# USB_SATA.net
KiCad netlist of a schematic drawn in Altium Designer
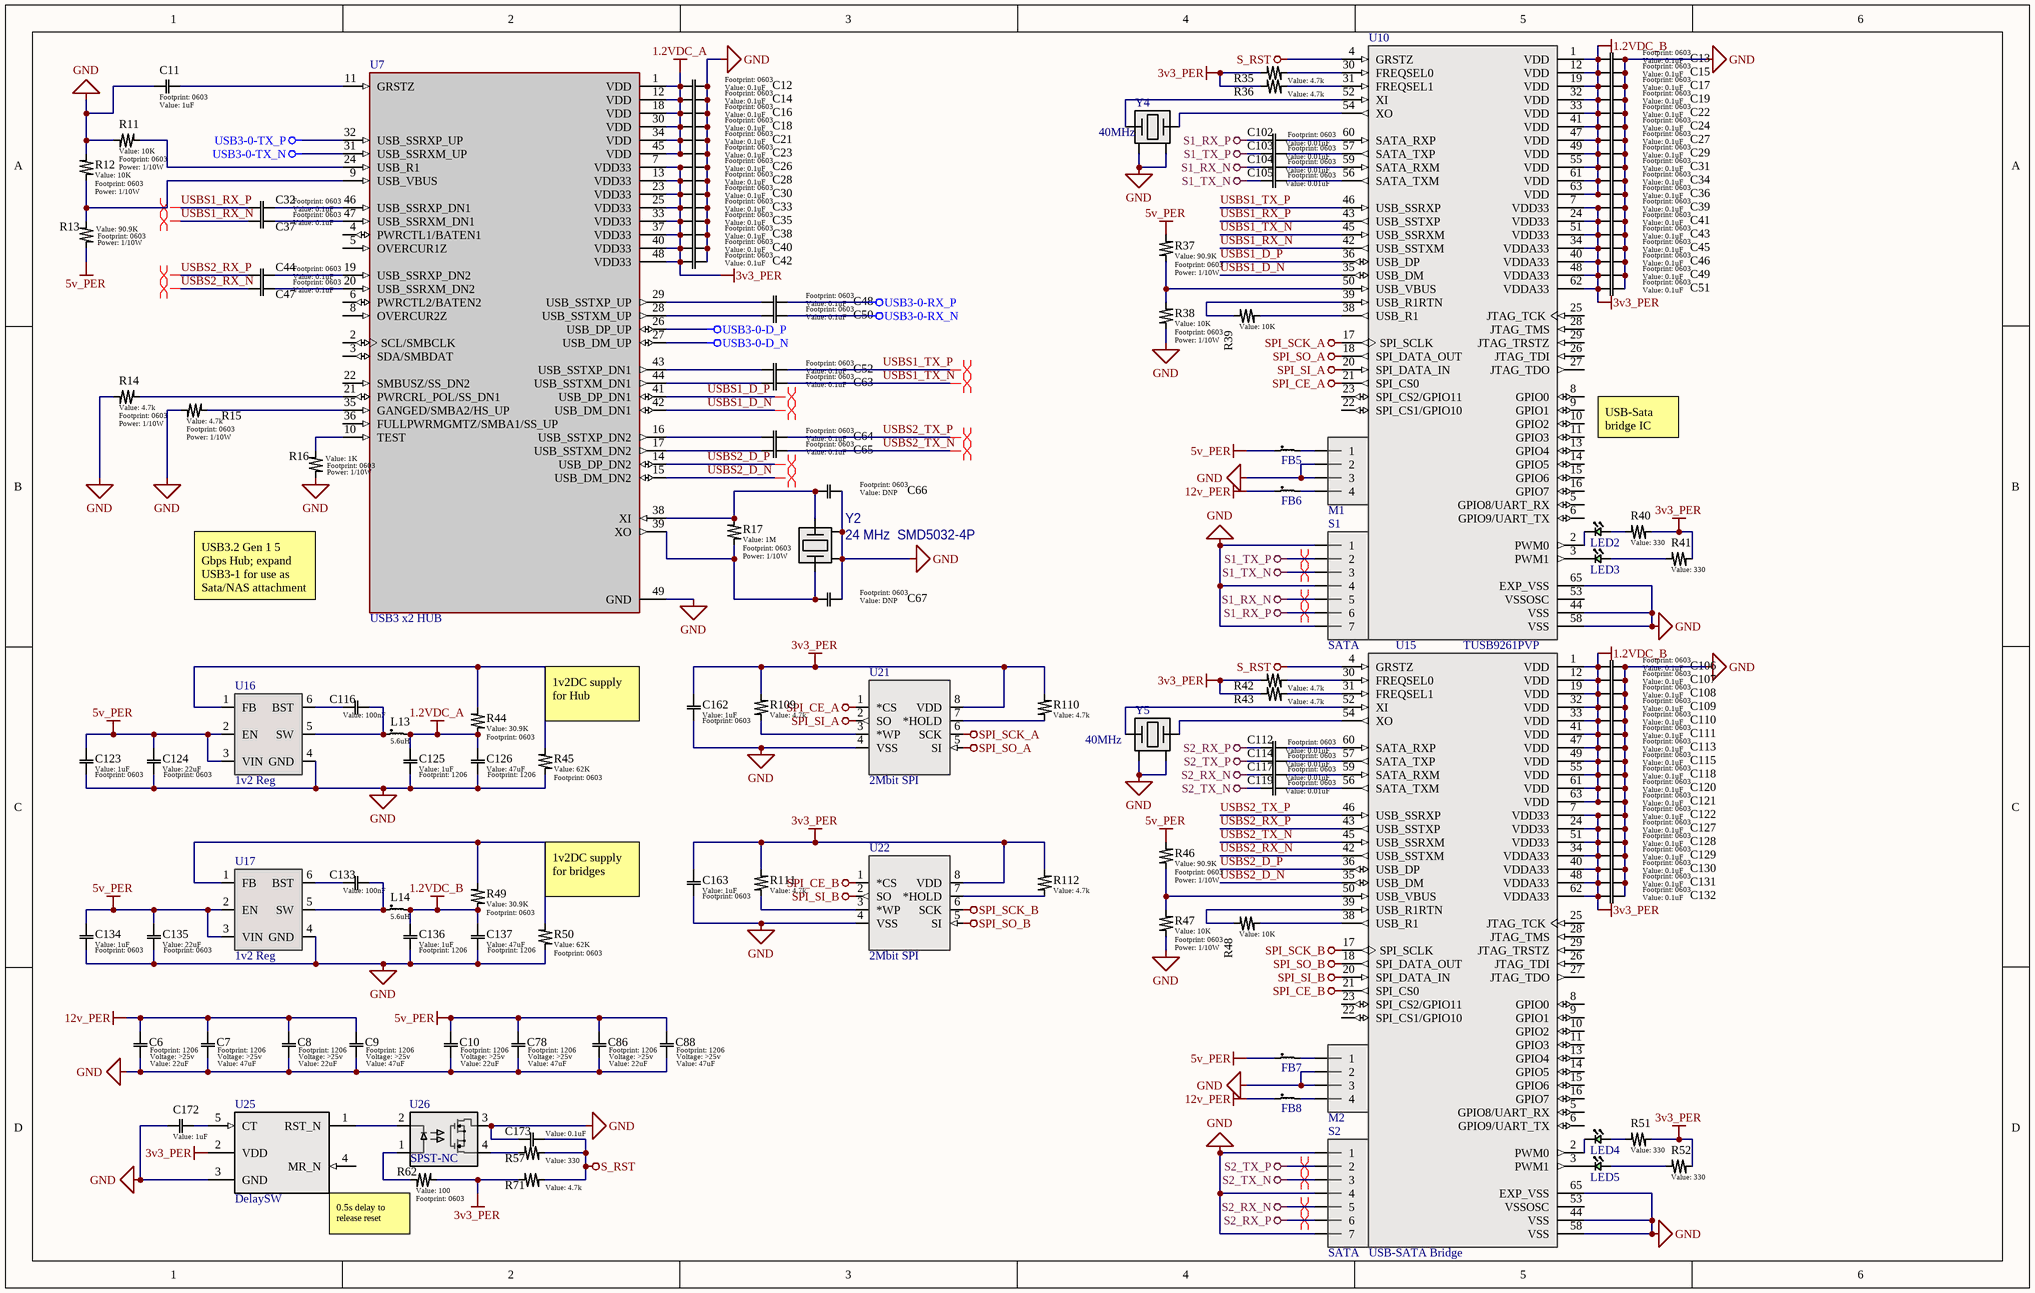
[diagram p0: USB_SATA.SchDoc]

(export (version "E")
  (design (tool "Eeschema 10.0.6"))
  (components
    (comp (ref "C6")
      (value "22uF")
      (footprint "1206")
      (fields
        (field (name "VOLTAGE") ">25v")
        (field (name "TOLERANCE") "20%")
        (field (name "Comment") "Generic Capacitor")
      )
      (libsource (lib "Capacitors") (part "Generic Capacitor"))
    )
    (comp (ref "C7")
      (value "47uF")
      (footprint "1206")
      (fields
        (field (name "VOLTAGE") ">25v")
        (field (name "TOLERANCE") "20%")
        (field (name "Comment") "Generic Capacitor")
      )
      (libsource (lib "Capacitors") (part "Generic Capacitor"))
    )
    (comp (ref "C8")
      (value "22uF")
      (footprint "1206")
      (fields
        (field (name "VOLTAGE") ">25v")
        (field (name "TOLERANCE") "20%")
        (field (name "Comment") "Generic Capacitor")
      )
      (libsource (lib "Capacitors") (part "Generic Capacitor"))
    )
    (comp (ref "C9")
      (value "47uF")
      (footprint "1206")
      (fields
        (field (name "VOLTAGE") ">25v")
        (field (name "TOLERANCE") "20%")
        (field (name "Comment") "Generic Capacitor")
      )
      (libsource (lib "Capacitors") (part "Generic Capacitor"))
    )
    (comp (ref "C10")
      (value "22uF")
      (footprint "1206")
      (fields
        (field (name "VOLTAGE") ">25v")
        (field (name "TOLERANCE") "20%")
        (field (name "Comment") "Generic Capacitor")
      )
      (libsource (lib "Capacitors") (part "Generic Capacitor"))
    )
    (comp (ref "C11")
      (value "1uF")
      (footprint "0603")
      (fields
        (field (name "VOLTAGE") ">10V")
        (field (name "TOLERANCE") "10%")
        (field (name "Comment") "Generic Capacitor")
      )
      (libsource (lib "Capacitors") (part "Generic Capacitor"))
    )
    (comp (ref "C12")
      (value "0.1uF")
      (footprint "0603")
      (fields
        (field (name "VOLTAGE") "10V")
        (field (name "TOLERANCE") "10%")
        (field (name "Comment") "Generic Capacitor")
      )
      (libsource (lib "Capacitors") (part "Generic Capacitor"))
    )
    (comp (ref "C13")
      (value "0.1uF")
      (footprint "0603")
      (fields
        (field (name "VOLTAGE") "10V")
        (field (name "TOLERANCE") "10%")
        (field (name "Comment") "Generic Capacitor")
      )
      (libsource (lib "Capacitors") (part "Generic Capacitor"))
    )
    (comp (ref "C14")
      (value "0.1uF")
      (footprint "0603")
      (fields
        (field (name "VOLTAGE") "10V")
        (field (name "TOLERANCE") "10%")
        (field (name "Comment") "Generic Capacitor")
      )
      (libsource (lib "Capacitors") (part "Generic Capacitor"))
    )
    (comp (ref "C15")
      (value "0.1uF")
      (footprint "0603")
      (fields
        (field (name "VOLTAGE") "10V")
        (field (name "TOLERANCE") "10%")
        (field (name "Comment") "Generic Capacitor")
      )
      (libsource (lib "Capacitors") (part "Generic Capacitor"))
    )
    (comp (ref "C16")
      (value "0.1uF")
      (footprint "0603")
      (fields
        (field (name "VOLTAGE") "10V")
        (field (name "TOLERANCE") "10%")
        (field (name "Comment") "Generic Capacitor")
      )
      (libsource (lib "Capacitors") (part "Generic Capacitor"))
    )
    (comp (ref "C17")
      (value "0.1uF")
      (footprint "0603")
      (fields
        (field (name "VOLTAGE") "10V")
        (field (name "TOLERANCE") "10%")
        (field (name "Comment") "Generic Capacitor")
      )
      (libsource (lib "Capacitors") (part "Generic Capacitor"))
    )
    (comp (ref "C18")
      (value "0.1uF")
      (footprint "0603")
      (fields
        (field (name "VOLTAGE") "10V")
        (field (name "TOLERANCE") "10%")
        (field (name "Comment") "Generic Capacitor")
      )
      (libsource (lib "Capacitors") (part "Generic Capacitor"))
    )
    (comp (ref "C19")
      (value "0.1uF")
      (footprint "0603")
      (fields
        (field (name "VOLTAGE") "10V")
        (field (name "TOLERANCE") "10%")
        (field (name "Comment") "Generic Capacitor")
      )
      (libsource (lib "Capacitors") (part "Generic Capacitor"))
    )
    (comp (ref "C21")
      (value "0.1uF")
      (footprint "0603")
      (fields
        (field (name "VOLTAGE") "10V")
        (field (name "TOLERANCE") "10%")
        (field (name "Comment") "Generic Capacitor")
      )
      (libsource (lib "Capacitors") (part "Generic Capacitor"))
    )
    (comp (ref "C22")
      (value "0.1uF")
      (footprint "0603")
      (fields
        (field (name "VOLTAGE") "10V")
        (field (name "TOLERANCE") "10%")
        (field (name "Comment") "Generic Capacitor")
      )
      (libsource (lib "Capacitors") (part "Generic Capacitor"))
    )
    (comp (ref "C23")
      (value "0.1uF")
      (footprint "0603")
      (fields
        (field (name "VOLTAGE") "10V")
        (field (name "TOLERANCE") "10%")
        (field (name "Comment") "Generic Capacitor")
      )
      (libsource (lib "Capacitors") (part "Generic Capacitor"))
    )
    (comp (ref "C24")
      (value "0.1uF")
      (footprint "0603")
      (fields
        (field (name "VOLTAGE") "10V")
        (field (name "TOLERANCE") "10%")
        (field (name "Comment") "Generic Capacitor")
      )
      (libsource (lib "Capacitors") (part "Generic Capacitor"))
    )
    (comp (ref "C26")
      (value "0.1uF")
      (footprint "0603")
      (fields
        (field (name "VOLTAGE") "10V")
        (field (name "TOLERANCE") "10%")
        (field (name "Comment") "Generic Capacitor")
      )
      (libsource (lib "Capacitors") (part "Generic Capacitor"))
    )
    (comp (ref "C27")
      (value "0.1uF")
      (footprint "0603")
      (fields
        (field (name "VOLTAGE") "10V")
        (field (name "TOLERANCE") "10%")
        (field (name "Comment") "Generic Capacitor")
      )
      (libsource (lib "Capacitors") (part "Generic Capacitor"))
    )
    (comp (ref "C28")
      (value "0.1uF")
      (footprint "0603")
      (fields
        (field (name "VOLTAGE") "10V")
        (field (name "TOLERANCE") "10%")
        (field (name "Comment") "Generic Capacitor")
      )
      (libsource (lib "Capacitors") (part "Generic Capacitor"))
    )
    (comp (ref "C29")
      (value "0.1uF")
      (footprint "0603")
      (fields
        (field (name "VOLTAGE") "10V")
        (field (name "TOLERANCE") "10%")
        (field (name "Comment") "Generic Capacitor")
      )
      (libsource (lib "Capacitors") (part "Generic Capacitor"))
    )
    (comp (ref "C30")
      (value "0.1uF")
      (footprint "0603")
      (fields
        (field (name "VOLTAGE") "10V")
        (field (name "TOLERANCE") "10%")
        (field (name "Comment") "Generic Capacitor")
      )
      (libsource (lib "Capacitors") (part "Generic Capacitor"))
    )
    (comp (ref "C31")
      (value "0.1uF")
      (footprint "0603")
      (fields
        (field (name "VOLTAGE") "10V")
        (field (name "TOLERANCE") "10%")
        (field (name "Comment") "Generic Capacitor")
      )
      (libsource (lib "Capacitors") (part "Generic Capacitor"))
    )
    (comp (ref "C32")
      (value "0.1uF")
      (footprint "0603")
      (fields
        (field (name "VOLTAGE") "10V")
        (field (name "TOLERANCE") "10%")
        (field (name "Comment") "Generic Capacitor")
      )
      (libsource (lib "Capacitors") (part "Generic Capacitor"))
    )
    (comp (ref "C33")
      (value "0.1uF")
      (footprint "0603")
      (fields
        (field (name "VOLTAGE") "10V")
        (field (name "TOLERANCE") "10%")
        (field (name "Comment") "Generic Capacitor")
      )
      (libsource (lib "Capacitors") (part "Generic Capacitor"))
    )
    (comp (ref "C34")
      (value "0.1uF")
      (footprint "0603")
      (fields
        (field (name "VOLTAGE") "10V")
        (field (name "TOLERANCE") "10%")
        (field (name "Comment") "Generic Capacitor")
      )
      (libsource (lib "Capacitors") (part "Generic Capacitor"))
    )
    (comp (ref "C35")
      (value "0.1uF")
      (footprint "0603")
      (fields
        (field (name "VOLTAGE") "10V")
        (field (name "TOLERANCE") "10%")
        (field (name "Comment") "Generic Capacitor")
      )
      (libsource (lib "Capacitors") (part "Generic Capacitor"))
    )
    (comp (ref "C36")
      (value "0.1uF")
      (footprint "0603")
      (fields
        (field (name "VOLTAGE") "10V")
        (field (name "TOLERANCE") "10%")
        (field (name "Comment") "Generic Capacitor")
      )
      (libsource (lib "Capacitors") (part "Generic Capacitor"))
    )
    (comp (ref "C37")
      (value "0.1uF")
      (footprint "0603")
      (fields
        (field (name "VOLTAGE") "10V")
        (field (name "TOLERANCE") "10%")
        (field (name "Comment") "Generic Capacitor")
      )
      (libsource (lib "Capacitors") (part "Generic Capacitor"))
    )
    (comp (ref "C38")
      (value "0.1uF")
      (footprint "0603")
      (fields
        (field (name "VOLTAGE") "10V")
        (field (name "TOLERANCE") "10%")
        (field (name "Comment") "Generic Capacitor")
      )
      (libsource (lib "Capacitors") (part "Generic Capacitor"))
    )
    (comp (ref "C39")
      (value "0.1uF")
      (footprint "0603")
      (fields
        (field (name "VOLTAGE") "10V")
        (field (name "TOLERANCE") "10%")
        (field (name "Comment") "Generic Capacitor")
      )
      (libsource (lib "Capacitors") (part "Generic Capacitor"))
    )
    (comp (ref "C40")
      (value "0.1uF")
      (footprint "0603")
      (fields
        (field (name "VOLTAGE") "10V")
        (field (name "TOLERANCE") "10%")
        (field (name "Comment") "Generic Capacitor")
      )
      (libsource (lib "Capacitors") (part "Generic Capacitor"))
    )
    (comp (ref "C41")
      (value "0.1uF")
      (footprint "0603")
      (fields
        (field (name "VOLTAGE") "10V")
        (field (name "TOLERANCE") "10%")
        (field (name "Comment") "Generic Capacitor")
      )
      (libsource (lib "Capacitors") (part "Generic Capacitor"))
    )
    (comp (ref "C42")
      (value "0.1uF")
      (footprint "0603")
      (fields
        (field (name "VOLTAGE") "10V")
        (field (name "TOLERANCE") "10%")
        (field (name "Comment") "Generic Capacitor")
      )
      (libsource (lib "Capacitors") (part "Generic Capacitor"))
    )
    (comp (ref "C43")
      (value "0.1uF")
      (footprint "0603")
      (fields
        (field (name "VOLTAGE") "10V")
        (field (name "TOLERANCE") "10%")
        (field (name "Comment") "Generic Capacitor")
      )
      (libsource (lib "Capacitors") (part "Generic Capacitor"))
    )
    (comp (ref "C44")
      (value "0.1uF")
      (footprint "0603")
      (fields
        (field (name "VOLTAGE") "10V")
        (field (name "TOLERANCE") "10%")
        (field (name "Comment") "Generic Capacitor")
      )
      (libsource (lib "Capacitors") (part "Generic Capacitor"))
    )
    (comp (ref "C45")
      (value "0.1uF")
      (footprint "0603")
      (fields
        (field (name "VOLTAGE") "10V")
        (field (name "TOLERANCE") "10%")
        (field (name "Comment") "Generic Capacitor")
      )
      (libsource (lib "Capacitors") (part "Generic Capacitor"))
    )
    (comp (ref "C46")
      (value "0.1uF")
      (footprint "0603")
      (fields
        (field (name "VOLTAGE") "10V")
        (field (name "TOLERANCE") "10%")
        (field (name "Comment") "Generic Capacitor")
      )
      (libsource (lib "Capacitors") (part "Generic Capacitor"))
    )
    (comp (ref "C47")
      (value "0.1uF")
      (footprint "0603")
      (fields
        (field (name "VOLTAGE") "10V")
        (field (name "TOLERANCE") "10%")
        (field (name "Comment") "Generic Capacitor")
      )
      (libsource (lib "Capacitors") (part "Generic Capacitor"))
    )
    (comp (ref "C48")
      (value "0.1uF")
      (footprint "0603")
      (fields
        (field (name "VOLTAGE") "10V")
        (field (name "TOLERANCE") "10%")
        (field (name "Comment") "Generic Capacitor")
      )
      (libsource (lib "Capacitors") (part "Generic Capacitor"))
    )
    (comp (ref "C49")
      (value "0.1uF")
      (footprint "0603")
      (fields
        (field (name "VOLTAGE") "10V")
        (field (name "TOLERANCE") "10%")
        (field (name "Comment") "Generic Capacitor")
      )
      (libsource (lib "Capacitors") (part "Generic Capacitor"))
    )
    (comp (ref "C50")
      (value "0.1uF")
      (footprint "0603")
      (fields
        (field (name "VOLTAGE") "10V")
        (field (name "TOLERANCE") "10%")
        (field (name "Comment") "Generic Capacitor")
      )
      (libsource (lib "Capacitors") (part "Generic Capacitor"))
    )
    (comp (ref "C51")
      (value "0.1uF")
      (footprint "0603")
      (fields
        (field (name "VOLTAGE") "10V")
        (field (name "TOLERANCE") "10%")
        (field (name "Comment") "Generic Capacitor")
      )
      (libsource (lib "Capacitors") (part "Generic Capacitor"))
    )
    (comp (ref "C52")
      (value "0.1uF")
      (footprint "0603")
      (fields
        (field (name "VOLTAGE") "10V")
        (field (name "TOLERANCE") "10%")
        (field (name "Comment") "Generic Capacitor")
      )
      (libsource (lib "Capacitors") (part "Generic Capacitor"))
    )
    (comp (ref "C63")
      (value "0.1uF")
      (footprint "0603")
      (fields
        (field (name "VOLTAGE") "10V")
        (field (name "TOLERANCE") "10%")
        (field (name "Comment") "Generic Capacitor")
      )
      (libsource (lib "Capacitors") (part "Generic Capacitor"))
    )
    (comp (ref "C64")
      (value "0.1uF")
      (footprint "0603")
      (fields
        (field (name "VOLTAGE") "10V")
        (field (name "TOLERANCE") "10%")
        (field (name "Comment") "Generic Capacitor")
      )
      (libsource (lib "Capacitors") (part "Generic Capacitor"))
    )
    (comp (ref "C65")
      (value "0.1uF")
      (footprint "0603")
      (fields
        (field (name "VOLTAGE") "10V")
        (field (name "TOLERANCE") "10%")
        (field (name "Comment") "Generic Capacitor")
      )
      (libsource (lib "Capacitors") (part "Generic Capacitor"))
    )
    (comp (ref "C66")
      (value "DNP")
      (footprint "0603")
      (fields
        (field (name "VOLTAGE") ">10V")
        (field (name "TOLERANCE") "10%")
        (field (name "Comment") "Generic Capacitor")
      )
      (libsource (lib "Capacitors") (part "Generic Capacitor"))
    )
    (comp (ref "C67")
      (value "DNP")
      (footprint "0603")
      (fields
        (field (name "VOLTAGE") ">10V")
        (field (name "TOLERANCE") "10%")
        (field (name "Comment") "Generic Capacitor")
      )
      (libsource (lib "Capacitors") (part "Generic Capacitor"))
    )
    (comp (ref "C78")
      (value "47uF")
      (footprint "1206")
      (fields
        (field (name "VOLTAGE") ">25v")
        (field (name "TOLERANCE") "20%")
        (field (name "Comment") "Generic Capacitor")
      )
      (libsource (lib "Capacitors") (part "Generic Capacitor"))
    )
    (comp (ref "C86")
      (value "22uF")
      (footprint "1206")
      (fields
        (field (name "VOLTAGE") ">25v")
        (field (name "TOLERANCE") "20%")
        (field (name "Comment") "Generic Capacitor")
      )
      (libsource (lib "Capacitors") (part "Generic Capacitor"))
    )
    (comp (ref "C88")
      (value "47uF")
      (footprint "1206")
      (fields
        (field (name "VOLTAGE") ">25v")
        (field (name "TOLERANCE") "20%")
        (field (name "Comment") "Generic Capacitor")
      )
      (libsource (lib "Capacitors") (part "Generic Capacitor"))
    )
    (comp (ref "C102")
      (value "0.01uF")
      (footprint "0603")
      (fields
        (field (name "VOLTAGE") "10V")
        (field (name "TOLERANCE") "10%")
        (field (name "Comment") "Generic Capacitor")
      )
      (libsource (lib "Capacitors") (part "Generic Capacitor"))
    )
    (comp (ref "C103")
      (value "0.01uF")
      (footprint "0603")
      (fields
        (field (name "VOLTAGE") "10V")
        (field (name "TOLERANCE") "10%")
        (field (name "Comment") "Generic Capacitor")
      )
      (libsource (lib "Capacitors") (part "Generic Capacitor"))
    )
    (comp (ref "C104")
      (value "0.01uF")
      (footprint "0603")
      (fields
        (field (name "VOLTAGE") "10V")
        (field (name "TOLERANCE") "10%")
        (field (name "Comment") "Generic Capacitor")
      )
      (libsource (lib "Capacitors") (part "Generic Capacitor"))
    )
    (comp (ref "C105")
      (value "0.01uF")
      (footprint "0603")
      (fields
        (field (name "VOLTAGE") "10V")
        (field (name "TOLERANCE") "10%")
        (field (name "Comment") "Generic Capacitor")
      )
      (libsource (lib "Capacitors") (part "Generic Capacitor"))
    )
    (comp (ref "C106")
      (value "0.1uF")
      (footprint "0603")
      (fields
        (field (name "VOLTAGE") "10V")
        (field (name "TOLERANCE") "10%")
        (field (name "Comment") "Generic Capacitor")
      )
      (libsource (lib "Capacitors") (part "Generic Capacitor"))
    )
    (comp (ref "C107")
      (value "0.1uF")
      (footprint "0603")
      (fields
        (field (name "VOLTAGE") "10V")
        (field (name "TOLERANCE") "10%")
        (field (name "Comment") "Generic Capacitor")
      )
      (libsource (lib "Capacitors") (part "Generic Capacitor"))
    )
    (comp (ref "C108")
      (value "0.1uF")
      (footprint "0603")
      (fields
        (field (name "VOLTAGE") "10V")
        (field (name "TOLERANCE") "10%")
        (field (name "Comment") "Generic Capacitor")
      )
      (libsource (lib "Capacitors") (part "Generic Capacitor"))
    )
    (comp (ref "C109")
      (value "0.1uF")
      (footprint "0603")
      (fields
        (field (name "VOLTAGE") "10V")
        (field (name "TOLERANCE") "10%")
        (field (name "Comment") "Generic Capacitor")
      )
      (libsource (lib "Capacitors") (part "Generic Capacitor"))
    )
    (comp (ref "C110")
      (value "0.1uF")
      (footprint "0603")
      (fields
        (field (name "VOLTAGE") "10V")
        (field (name "TOLERANCE") "10%")
        (field (name "Comment") "Generic Capacitor")
      )
      (libsource (lib "Capacitors") (part "Generic Capacitor"))
    )
    (comp (ref "C111")
      (value "0.1uF")
      (footprint "0603")
      (fields
        (field (name "VOLTAGE") "10V")
        (field (name "TOLERANCE") "10%")
        (field (name "Comment") "Generic Capacitor")
      )
      (libsource (lib "Capacitors") (part "Generic Capacitor"))
    )
    (comp (ref "C112")
      (value "0.01uF")
      (footprint "0603")
      (fields
        (field (name "VOLTAGE") "10V")
        (field (name "TOLERANCE") "10%")
        (field (name "Comment") "Generic Capacitor")
      )
      (libsource (lib "Capacitors") (part "Generic Capacitor"))
    )
    (comp (ref "C113")
      (value "0.1uF")
      (footprint "0603")
      (fields
        (field (name "VOLTAGE") "10V")
        (field (name "TOLERANCE") "10%")
        (field (name "Comment") "Generic Capacitor")
      )
      (libsource (lib "Capacitors") (part "Generic Capacitor"))
    )
    (comp (ref "C114")
      (value "0.01uF")
      (footprint "0603")
      (fields
        (field (name "VOLTAGE") "10V")
        (field (name "TOLERANCE") "10%")
        (field (name "Comment") "Generic Capacitor")
      )
      (libsource (lib "Capacitors") (part "Generic Capacitor"))
    )
    (comp (ref "C115")
      (value "0.1uF")
      (footprint "0603")
      (fields
        (field (name "VOLTAGE") "10V")
        (field (name "TOLERANCE") "10%")
        (field (name "Comment") "Generic Capacitor")
      )
      (libsource (lib "Capacitors") (part "Generic Capacitor"))
    )
    (comp (ref "C116")
      (value "100nF")
      (footprint "0603")
      (fields
        (field (name "VOLTAGE") ">10V")
        (field (name "TOLERANCE") "10%")
        (field (name "Comment") "Generic Capacitor")
      )
      (libsource (lib "Capacitors") (part "Generic Capacitor"))
    )
    (comp (ref "C117")
      (value "0.01uF")
      (footprint "0603")
      (fields
        (field (name "VOLTAGE") "10V")
        (field (name "TOLERANCE") "10%")
        (field (name "Comment") "Generic Capacitor")
      )
      (libsource (lib "Capacitors") (part "Generic Capacitor"))
    )
    (comp (ref "C118")
      (value "0.1uF")
      (footprint "0603")
      (fields
        (field (name "VOLTAGE") "10V")
        (field (name "TOLERANCE") "10%")
        (field (name "Comment") "Generic Capacitor")
      )
      (libsource (lib "Capacitors") (part "Generic Capacitor"))
    )
    (comp (ref "C119")
      (value "0.01uF")
      (footprint "0603")
      (fields
        (field (name "VOLTAGE") "10V")
        (field (name "TOLERANCE") "10%")
        (field (name "Comment") "Generic Capacitor")
      )
      (libsource (lib "Capacitors") (part "Generic Capacitor"))
    )
    (comp (ref "C120")
      (value "0.1uF")
      (footprint "0603")
      (fields
        (field (name "VOLTAGE") "10V")
        (field (name "TOLERANCE") "10%")
        (field (name "Comment") "Generic Capacitor")
      )
      (libsource (lib "Capacitors") (part "Generic Capacitor"))
    )
    (comp (ref "C121")
      (value "0.1uF")
      (footprint "0603")
      (fields
        (field (name "VOLTAGE") "10V")
        (field (name "TOLERANCE") "10%")
        (field (name "Comment") "Generic Capacitor")
      )
      (libsource (lib "Capacitors") (part "Generic Capacitor"))
    )
    (comp (ref "C122")
      (value "0.1uF")
      (footprint "0603")
      (fields
        (field (name "VOLTAGE") "10V")
        (field (name "TOLERANCE") "10%")
        (field (name "Comment") "Generic Capacitor")
      )
      (libsource (lib "Capacitors") (part "Generic Capacitor"))
    )
    (comp (ref "C123")
      (value "1uF")
      (footprint "0603")
      (fields
        (field (name "VOLTAGE") ">10V")
        (field (name "TOLERANCE") "10%")
        (field (name "Comment") "Generic Capacitor")
      )
      (libsource (lib "Capacitors") (part "Generic Capacitor"))
    )
    (comp (ref "C124")
      (value "22uF")
      (footprint "0603")
      (fields
        (field (name "VOLTAGE") ">10V")
        (field (name "TOLERANCE") "10%")
        (field (name "Comment") "Generic Capacitor")
      )
      (libsource (lib "Capacitors") (part "Generic Capacitor"))
    )
    (comp (ref "C125")
      (value "1uF")
      (footprint "1206")
      (fields
        (field (name "VOLTAGE") ">10V")
        (field (name "TOLERANCE") "10%")
        (field (name "Comment") "Generic Capacitor")
      )
      (libsource (lib "Capacitors") (part "Generic Capacitor"))
    )
    (comp (ref "C126")
      (value "47uF")
      (footprint "1206")
      (fields
        (field (name "VOLTAGE") ">10V")
        (field (name "TOLERANCE") "10%")
        (field (name "Comment") "Generic Capacitor")
      )
      (libsource (lib "Capacitors") (part "Generic Capacitor"))
    )
    (comp (ref "C127")
      (value "0.1uF")
      (footprint "0603")
      (fields
        (field (name "VOLTAGE") "10V")
        (field (name "TOLERANCE") "10%")
        (field (name "Comment") "Generic Capacitor")
      )
      (libsource (lib "Capacitors") (part "Generic Capacitor"))
    )
    (comp (ref "C128")
      (value "0.1uF")
      (footprint "0603")
      (fields
        (field (name "VOLTAGE") "10V")
        (field (name "TOLERANCE") "10%")
        (field (name "Comment") "Generic Capacitor")
      )
      (libsource (lib "Capacitors") (part "Generic Capacitor"))
    )
    (comp (ref "C129")
      (value "0.1uF")
      (footprint "0603")
      (fields
        (field (name "VOLTAGE") "10V")
        (field (name "TOLERANCE") "10%")
        (field (name "Comment") "Generic Capacitor")
      )
      (libsource (lib "Capacitors") (part "Generic Capacitor"))
    )
    (comp (ref "C130")
      (value "0.1uF")
      (footprint "0603")
      (fields
        (field (name "VOLTAGE") "10V")
        (field (name "TOLERANCE") "10%")
        (field (name "Comment") "Generic Capacitor")
      )
      (libsource (lib "Capacitors") (part "Generic Capacitor"))
    )
    (comp (ref "C131")
      (value "0.1uF")
      (footprint "0603")
      (fields
        (field (name "VOLTAGE") "10V")
        (field (name "TOLERANCE") "10%")
        (field (name "Comment") "Generic Capacitor")
      )
      (libsource (lib "Capacitors") (part "Generic Capacitor"))
    )
    (comp (ref "C132")
      (value "0.1uF")
      (footprint "0603")
      (fields
        (field (name "VOLTAGE") "10V")
        (field (name "TOLERANCE") "10%")
        (field (name "Comment") "Generic Capacitor")
      )
      (libsource (lib "Capacitors") (part "Generic Capacitor"))
    )
    (comp (ref "C133")
      (value "100nF")
      (footprint "0603")
      (fields
        (field (name "VOLTAGE") ">10V")
        (field (name "TOLERANCE") "10%")
        (field (name "Comment") "Generic Capacitor")
      )
      (libsource (lib "Capacitors") (part "Generic Capacitor"))
    )
    (comp (ref "C134")
      (value "1uF")
      (footprint "0603")
      (fields
        (field (name "VOLTAGE") ">10V")
        (field (name "TOLERANCE") "10%")
        (field (name "Comment") "Generic Capacitor")
      )
      (libsource (lib "Capacitors") (part "Generic Capacitor"))
    )
    (comp (ref "C135")
      (value "22uF")
      (footprint "0603")
      (fields
        (field (name "VOLTAGE") ">10V")
        (field (name "TOLERANCE") "10%")
        (field (name "Comment") "Generic Capacitor")
      )
      (libsource (lib "Capacitors") (part "Generic Capacitor"))
    )
    (comp (ref "C136")
      (value "1uF")
      (footprint "1206")
      (fields
        (field (name "VOLTAGE") ">10V")
        (field (name "TOLERANCE") "10%")
        (field (name "Comment") "Generic Capacitor")
      )
      (libsource (lib "Capacitors") (part "Generic Capacitor"))
    )
    (comp (ref "C137")
      (value "47uF")
      (footprint "1206")
      (fields
        (field (name "VOLTAGE") ">10V")
        (field (name "TOLERANCE") "10%")
        (field (name "Comment") "Generic Capacitor")
      )
      (libsource (lib "Capacitors") (part "Generic Capacitor"))
    )
    (comp (ref "C162")
      (value "1uF")
      (footprint "0603")
      (fields
        (field (name "VOLTAGE") ">10V")
        (field (name "TOLERANCE") "10%")
        (field (name "Comment") "Generic Capacitor")
      )
      (libsource (lib "Capacitors") (part "Generic Capacitor"))
    )
    (comp (ref "C163")
      (value "1uF")
      (footprint "0603")
      (fields
        (field (name "VOLTAGE") ">10V")
        (field (name "TOLERANCE") "10%")
        (field (name "Comment") "Generic Capacitor")
      )
      (libsource (lib "Capacitors") (part "Generic Capacitor"))
    )
    (comp (ref "C172")
      (value "1uF")
      (footprint "0603")
      (fields
        (field (name "VOLTAGE") "10V")
        (field (name "TOLERANCE") "10%")
        (field (name "Comment") "Generic Capacitor")
      )
      (libsource (lib "Capacitors") (part "Generic Capacitor"))
    )
    (comp (ref "C173")
      (value "0.1uF")
      (footprint "0603")
      (fields
        (field (name "VOLTAGE") "10V")
        (field (name "TOLERANCE") "10%")
        (field (name "Comment") "Generic Capacitor")
      )
      (libsource (lib "Capacitors") (part "Generic Capacitor"))
    )
    (comp (ref "FB5")
      (value "1206 Ferrite")
      (footprint "1206")
      (description "160 Ohms @ 100MHz 1 Power, Signal Line Ferrite Bead 1206 (3216 Metric) 6A 18mOhm")
      (libsource (lib "Inductors") (part "HI1206T161R-10"))
    )
    (comp (ref "FB6")
      (value "1206 Ferrite")
      (footprint "1206")
      (description "160 Ohms @ 100MHz 1 Power, Signal Line Ferrite Bead 1206 (3216 Metric) 6A 18mOhm")
      (libsource (lib "Inductors") (part "HI1206T161R-10"))
    )
    (comp (ref "FB7")
      (value "1206 Ferrite")
      (footprint "1206")
      (description "160 Ohms @ 100MHz 1 Power, Signal Line Ferrite Bead 1206 (3216 Metric) 6A 18mOhm")
      (libsource (lib "Inductors") (part "HI1206T161R-10"))
    )
    (comp (ref "FB8")
      (value "1206 Ferrite")
      (footprint "1206")
      (description "160 Ohms @ 100MHz 1 Power, Signal Line Ferrite Bead 1206 (3216 Metric) 6A 18mOhm")
      (libsource (lib "Inductors") (part "HI1206T161R-10"))
    )
    (comp (ref "L13")
      (value "5.6uH")
      (footprint "TMPC0402HP")
      (description "2A 5.6uH ±20% SMD Power Inductor")
      (libsource (lib "Inductors") (part "TMPC0402HP-5R6MG-Z02"))
    )
    (comp (ref "L14")
      (value "5.6uH")
      (footprint "TMPC0402HP")
      (description "2A 5.6uH ±20% SMD Power Inductor")
      (libsource (lib "Inductors") (part "TMPC0402HP-5R6MG-Z02"))
    )
    (comp (ref "LED2")
      (value "LTST-C191KGKT")
      (footprint "0603 (1608 Metric) Concave")
      (description "LED Uni-Color Green 574nm 2-Pin Chip LED T/R")
      (libsource (lib "Gamber - Johnson LLC") (part "LTST-C191KGKT"))
    )
    (comp (ref "LED3")
      (value "LTST-C191KGKT")
      (footprint "0603 (1608 Metric) Concave")
      (description "LED Uni-Color Green 574nm 2-Pin Chip LED T/R")
      (libsource (lib "Gamber - Johnson LLC") (part "LTST-C191KGKT"))
    )
    (comp (ref "LED4")
      (value "LTST-C191KGKT")
      (footprint "0603 (1608 Metric) Concave")
      (description "LED Uni-Color Green 574nm 2-Pin Chip LED T/R")
      (libsource (lib "Gamber - Johnson LLC") (part "LTST-C191KGKT"))
    )
    (comp (ref "LED5")
      (value "LTST-C191KGKT")
      (footprint "0603 (1608 Metric) Concave")
      (description "LED Uni-Color Green 574nm 2-Pin Chip LED T/R")
      (libsource (lib "Gamber - Johnson LLC") (part "LTST-C191KGKT"))
    )
    (comp (ref "M1")
      (value "MATE-n-Lock")
      (footprint "794287-1")
      (description "4 Position Header Connector 0.200\" (5.08mm) Through Hole Tin")
      (libsource (lib "Connectors") (part "794287-1"))
    )
    (comp (ref "M2")
      (value "MATE-n-Lock")
      (footprint "794287-1")
      (description "4 Position Header Connector 0.200\" (5.08mm) Through Hole Tin")
      (libsource (lib "Connectors") (part "794287-1"))
    )
    (comp (ref "R11")
      (value "10K")
      (footprint "0603")
      (fields
        (field (name "TOLERANCE") "1%")
        (field (name "POWER") "1/10W")
        (field (name "Comment") "Generic Resistor")
      )
      (libsource (lib "Resistors") (part "Generic Resistor"))
    )
    (comp (ref "R12")
      (value "10K")
      (footprint "0603")
      (fields
        (field (name "TOLERANCE") "1%")
        (field (name "POWER") "1/10W")
        (field (name "Comment") "Generic Resistor")
      )
      (libsource (lib "Resistors") (part "Generic Resistor"))
    )
    (comp (ref "R13")
      (value "90.9K")
      (footprint "0603")
      (fields
        (field (name "TOLERANCE") "1%")
        (field (name "POWER") "1/10W")
        (field (name "Comment") "Generic Resistor")
      )
      (libsource (lib "Resistors") (part "Generic Resistor"))
    )
    (comp (ref "R14")
      (value "4.7k")
      (footprint "0603")
      (fields
        (field (name "TOLERANCE") "1%")
        (field (name "POWER") "1/10W")
        (field (name "Comment") "Generic Resistor")
      )
      (libsource (lib "Resistors") (part "Generic Resistor"))
    )
    (comp (ref "R15")
      (value "4.7k")
      (footprint "0603")
      (fields
        (field (name "TOLERANCE") "1%")
        (field (name "POWER") "1/10W")
        (field (name "Comment") "Generic Resistor")
      )
      (libsource (lib "Resistors") (part "Generic Resistor"))
    )
    (comp (ref "R16")
      (value "1K")
      (footprint "0603")
      (fields
        (field (name "TOLERANCE") "1%")
        (field (name "POWER") "1/10W")
        (field (name "Comment") "Generic Resistor")
      )
      (libsource (lib "Resistors") (part "Generic Resistor"))
    )
    (comp (ref "R17")
      (value "1M")
      (footprint "0603")
      (fields
        (field (name "TOLERANCE") "1%")
        (field (name "POWER") "1/10W")
        (field (name "Comment") "Generic Resistor")
      )
      (libsource (lib "Resistors") (part "Generic Resistor"))
    )
    (comp (ref "R35")
      (value "4.7k")
      (footprint "0603")
      (fields
        (field (name "TOLERANCE") "1%")
        (field (name "POWER") "1/10W")
        (field (name "Comment") "Generic Resistor")
      )
      (libsource (lib "Resistors") (part "Generic Resistor"))
    )
    (comp (ref "R36")
      (value "4.7k")
      (footprint "0603")
      (fields
        (field (name "TOLERANCE") "1%")
        (field (name "POWER") "1/10W")
        (field (name "Comment") "Generic Resistor")
      )
      (libsource (lib "Resistors") (part "Generic Resistor"))
    )
    (comp (ref "R37")
      (value "90.9K")
      (footprint "0603")
      (fields
        (field (name "TOLERANCE") "1%")
        (field (name "POWER") "1/10W")
        (field (name "Comment") "Generic Resistor")
      )
      (libsource (lib "Resistors") (part "Generic Resistor"))
    )
    (comp (ref "R38")
      (value "10K")
      (footprint "0603")
      (fields
        (field (name "TOLERANCE") "1%")
        (field (name "POWER") "1/10W")
        (field (name "Comment") "Generic Resistor")
      )
      (libsource (lib "Resistors") (part "Generic Resistor"))
    )
    (comp (ref "R39")
      (value "10K")
      (footprint "0603")
      (fields
        (field (name "TOLERANCE") "1%")
        (field (name "POWER") "1/10W")
        (field (name "Comment") "Generic Resistor")
      )
      (libsource (lib "Resistors") (part "Generic Resistor"))
    )
    (comp (ref "R40")
      (value "330")
      (footprint "0603")
      (fields
        (field (name "TOLERANCE") "1%")
        (field (name "POWER") "1/10W")
        (field (name "Comment") "Generic Resistor")
      )
      (libsource (lib "Resistors") (part "Generic Resistor"))
    )
    (comp (ref "R41")
      (value "330")
      (footprint "0603")
      (fields
        (field (name "TOLERANCE") "1%")
        (field (name "POWER") "1/10W")
        (field (name "Comment") "Generic Resistor")
      )
      (libsource (lib "Resistors") (part "Generic Resistor"))
    )
    (comp (ref "R42")
      (value "4.7k")
      (footprint "0603")
      (fields
        (field (name "TOLERANCE") "1%")
        (field (name "POWER") "1/10W")
        (field (name "Comment") "Generic Resistor")
      )
      (libsource (lib "Resistors") (part "Generic Resistor"))
    )
    (comp (ref "R43")
      (value "4.7k")
      (footprint "0603")
      (fields
        (field (name "TOLERANCE") "1%")
        (field (name "POWER") "1/10W")
        (field (name "Comment") "Generic Resistor")
      )
      (libsource (lib "Resistors") (part "Generic Resistor"))
    )
    (comp (ref "R44")
      (value "30.9K")
      (footprint "0603")
      (fields
        (field (name "TOLERANCE") "1%")
        (field (name "POWER") "1/10W")
        (field (name "Comment") "Generic Resistor")
      )
      (libsource (lib "Resistors") (part "Generic Resistor"))
    )
    (comp (ref "R45")
      (value "62K")
      (footprint "0603")
      (fields
        (field (name "TOLERANCE") "1%")
        (field (name "POWER") "1/10W")
        (field (name "Comment") "Generic Resistor")
      )
      (libsource (lib "Resistors") (part "Generic Resistor"))
    )
    (comp (ref "R46")
      (value "90.9K")
      (footprint "0603")
      (fields
        (field (name "TOLERANCE") "1%")
        (field (name "POWER") "1/10W")
        (field (name "Comment") "Generic Resistor")
      )
      (libsource (lib "Resistors") (part "Generic Resistor"))
    )
    (comp (ref "R47")
      (value "10K")
      (footprint "0603")
      (fields
        (field (name "TOLERANCE") "1%")
        (field (name "POWER") "1/10W")
        (field (name "Comment") "Generic Resistor")
      )
      (libsource (lib "Resistors") (part "Generic Resistor"))
    )
    (comp (ref "R48")
      (value "10K")
      (footprint "0603")
      (fields
        (field (name "TOLERANCE") "1%")
        (field (name "POWER") "1/10W")
        (field (name "Comment") "Generic Resistor")
      )
      (libsource (lib "Resistors") (part "Generic Resistor"))
    )
    (comp (ref "R49")
      (value "30.9K")
      (footprint "0603")
      (fields
        (field (name "TOLERANCE") "1%")
        (field (name "POWER") "1/10W")
        (field (name "Comment") "Generic Resistor")
      )
      (libsource (lib "Resistors") (part "Generic Resistor"))
    )
    (comp (ref "R50")
      (value "62K")
      (footprint "0603")
      (fields
        (field (name "TOLERANCE") "1%")
        (field (name "POWER") "1/10W")
        (field (name "Comment") "Generic Resistor")
      )
      (libsource (lib "Resistors") (part "Generic Resistor"))
    )
    (comp (ref "R51")
      (value "330")
      (footprint "0603")
      (fields
        (field (name "TOLERANCE") "1%")
        (field (name "POWER") "1/10W")
        (field (name "Comment") "Generic Resistor")
      )
      (libsource (lib "Resistors") (part "Generic Resistor"))
    )
    (comp (ref "R52")
      (value "330")
      (footprint "0603")
      (fields
        (field (name "TOLERANCE") "1%")
        (field (name "POWER") "1/10W")
        (field (name "Comment") "Generic Resistor")
      )
      (libsource (lib "Resistors") (part "Generic Resistor"))
    )
    (comp (ref "R57")
      (value "330")
      (footprint "0603")
      (fields
        (field (name "TOLERANCE") "1%")
        (field (name "POWER") "1/10W")
        (field (name "Comment") "Generic Resistor")
      )
      (libsource (lib "Resistors") (part "Generic Resistor"))
    )
    (comp (ref "R62")
      (value "100")
      (footprint "0603")
      (fields
        (field (name "TOLERANCE") "1%")
        (field (name "POWER") "1/10W")
        (field (name "Comment") "Generic Resistor")
      )
      (libsource (lib "Resistors") (part "Generic Resistor"))
    )
    (comp (ref "R71")
      (value "4.7k")
      (footprint "0603")
      (fields
        (field (name "TOLERANCE") "1%")
        (field (name "POWER") "1/10W")
        (field (name "Comment") "Generic Resistor")
      )
      (libsource (lib "Resistors") (part "Generic Resistor"))
    )
    (comp (ref "R109")
      (value "4.7k")
      (footprint "0603")
      (fields
        (field (name "TOLERANCE") "1%")
        (field (name "POWER") "1/10W")
        (field (name "Comment") "Generic Resistor")
      )
      (libsource (lib "Resistors") (part "Generic Resistor"))
    )
    (comp (ref "R110")
      (value "4.7k")
      (footprint "0603")
      (fields
        (field (name "TOLERANCE") "1%")
        (field (name "POWER") "1/10W")
        (field (name "Comment") "Generic Resistor")
      )
      (libsource (lib "Resistors") (part "Generic Resistor"))
    )
    (comp (ref "R111")
      (value "4.7k")
      (footprint "0603")
      (fields
        (field (name "TOLERANCE") "1%")
        (field (name "POWER") "1/10W")
        (field (name "Comment") "Generic Resistor")
      )
      (libsource (lib "Resistors") (part "Generic Resistor"))
    )
    (comp (ref "R112")
      (value "4.7k")
      (footprint "0603")
      (fields
        (field (name "TOLERANCE") "1%")
        (field (name "POWER") "1/10W")
        (field (name "Comment") "Generic Resistor")
      )
      (libsource (lib "Resistors") (part "Generic Resistor"))
    )
    (comp (ref "S1")
      (value "SATA")
      (footprint "67800-8025")
      (description "7 Position SATA Header, Shrouded Connector Solder Through Hole")
      (libsource (lib "Connectors") (part "67800-8025"))
    )
    (comp (ref "S2")
      (value "SATA")
      (footprint "67800-8025")
      (description "7 Position SATA Header, Shrouded Connector Solder Through Hole")
      (libsource (lib "Connectors") (part "67800-8025"))
    )
    (comp (ref "U7")
      (value "USB3 x2 HUB")
      (footprint "HTQFP-48(7x7)")
      (description "USB Hub Controller USB 3.0")
      (libsource (lib "Hub ICs") (part "TUSB8020BPHP"))
    )
    (comp (ref "U10")
      (value "USB-SATA Bridge")
      (footprint "64-HTQFP (7x7)")
      (description "HDD, CD, DVD Drive Interface 64-HTQFP _7x7_")
      (fields
        (field (name "MF") "Texas Instruments")
        (field (name "DIGI-KEY_PART_NUMBER") "296-28827-ND")
        (field (name "MP") "TUSB9261PVP")
      )
      (libsource (lib "Misc ICs") (part "TUSB9261PVP"))
    )
    (comp (ref "U15")
      (value "USB-SATA Bridge")
      (footprint "64-HTQFP (7x7)")
      (description "HDD, CD, DVD Drive Interface 64-HTQFP _7x7_")
      (fields (field (name "MF") "Texas Instruments") (field (name "DIGI-KEY_PART_NUMBER") "296-28827-ND"))
      (libsource (lib "Misc ICs") (part "TUSB9261PVP"))
    )
    (comp (ref "U16")
      (value "1v2 Reg")
      (footprint "TSOT-23-6")
      (description "Step-down type Adjustable 2A 1.2V~12V 3.8V~32V TSOT-23-6 DC-DC Converter")
      (libsource (lib "Regulators") (part "AP63201WU-7"))
    )
    (comp (ref "U17")
      (value "1v2 Reg")
      (footprint "TSOT-23-6")
      (description "Step-down type Adjustable 2A 1.2V~12V 3.8V~32V TSOT-23-6 DC-DC Converter")
      (libsource (lib "Regulators") (part "AP63201WU-7"))
    )
    (comp (ref "U21")
      (value "2Mbit SPI")
      (footprint "8-SOIC (0.154\", 3.90mm Width)")
      (description "IC FLASH 2MBIT SPI 30MHZ 8SOP")
      (libsource (lib "Misc ICs") (part "LE25U20AMB-AH"))
    )
    (comp (ref "U22")
      (value "2Mbit SPI")
      (footprint "8-SOIC (0.154\", 3.90mm Width)")
      (description "IC FLASH 2MBIT SPI 30MHZ 8SOP")
      (libsource (lib "Misc ICs") (part "LE25U20AMB-AH"))
    )
    (comp (ref "U25")
      (value "DelaySW")
      (footprint "TSOT-23-5")
      (description "Supervisor Open Drain or Open Collector 1 Channel SOT-23-5\r\n2.2V Threshold")
      (libsource (lib "Switches") (part "TPS3840DL22DBVR"))
    )
    (comp (ref "U26")
      (value "SPST-NC")
      (footprint "4-SOP")
      (description "SSR RELAY SPST-NC 400MA 0-60V")
      (libsource (lib "Switches") (part "CPC1117N"))
    )
    (comp (ref "Y2")
      (value "24 MHz  SMD5032-4P")
      (footprint "ECS-240-18-30BQ-DS")
      (description "24 MHz ±30ppm Crystal 18pF 30 Ohms 4-SMD, No Lead")
      (libsource (lib "Gamber - Johnson LLC") (part "ECS-240-18-30BQ-DS"))
    )
    (comp (ref "Y4")
      (value "40MHz")
      (footprint "SMD3225-4P")
      (description "40MHz Surface Mount Crystal 10pF ±10ppm SMD3225-4P Crystal")
      (libsource (lib "Clock ICs") (part "L327S400H11L"))
    )
    (comp (ref "Y5")
      (value "40MHz")
      (footprint "SMD3225-4P")
      (description "40MHz Surface Mount Crystal 10pF ±10ppm SMD3225-4P Crystal")
      (libsource (lib "Clock ICs") (part "L327S400H11L"))
    )
  )
  (nets
    (net (code "1") (name "/USBS1_D_N") (class "Default")
      (node (ref "U10") (pin "35") (pinfunction "USB_DM_35") (pintype "bidirectional"))
      (node (ref "U7") (pin "42") (pinfunction "USB_DM_DN1_42") (pintype "bidirectional"))
    )
    (net (code "2") (name "/USBS1_D_P") (class "Default")
      (node (ref "U10") (pin "36") (pinfunction "USB_DP_36") (pintype "bidirectional"))
      (node (ref "U7") (pin "41") (pinfunction "USB_DP_DN1_41") (pintype "bidirectional"))
    )
    (net (code "3") (name "/USBS1_RX_N") (class "Default")
      (node (ref "C37") (pin "2") (pinfunction "2_2") (pintype "passive"))
      (node (ref "U10") (pin "42") (pinfunction "USB_SSTXM_42") (pintype "output"))
    )
    (net (code "4") (name "/USBS1_RX_P") (class "Default")
      (node (ref "C32") (pin "2") (pinfunction "2_2") (pintype "passive"))
      (node (ref "U10") (pin "43") (pinfunction "USB_SSTXP_43") (pintype "output"))
    )
    (net (code "5") (name "/USBS1_TX_N") (class "Default")
      (node (ref "C63") (pin "1") (pinfunction "1_1") (pintype "passive"))
      (node (ref "U10") (pin "45") (pinfunction "USB_SSRXM_45") (pintype "input"))
    )
    (net (code "6") (name "/USBS1_TX_P") (class "Default")
      (node (ref "C52") (pin "1") (pinfunction "1_1") (pintype "passive"))
      (node (ref "U10") (pin "46") (pinfunction "USB_SSRXP_46") (pintype "input"))
    )
    (net (code "7") (name "/USBS2_D_N") (class "Default")
      (node (ref "U15") (pin "35") (pinfunction "USB_DM_35") (pintype "bidirectional"))
      (node (ref "U7") (pin "15") (pinfunction "USB_DM_DN2_15") (pintype "bidirectional"))
    )
    (net (code "8") (name "/USBS2_D_P") (class "Default")
      (node (ref "U15") (pin "36") (pinfunction "USB_DP_36") (pintype "bidirectional"))
      (node (ref "U7") (pin "14") (pinfunction "USB_DP_DN2_14") (pintype "bidirectional"))
    )
    (net (code "9") (name "/USBS2_RX_N") (class "Default")
      (node (ref "C47") (pin "2") (pinfunction "2_2") (pintype "passive"))
      (node (ref "U15") (pin "42") (pinfunction "USB_SSTXM_42") (pintype "output"))
    )
    (net (code "10") (name "/USBS2_RX_P") (class "Default")
      (node (ref "C44") (pin "2") (pinfunction "2_2") (pintype "passive"))
      (node (ref "U15") (pin "43") (pinfunction "USB_SSTXP_43") (pintype "output"))
    )
    (net (code "11") (name "/USBS2_TX_N") (class "Default")
      (node (ref "C65") (pin "1") (pinfunction "1_1") (pintype "passive"))
      (node (ref "U15") (pin "45") (pinfunction "USB_SSRXM_45") (pintype "input"))
    )
    (net (code "12") (name "/USBS2_TX_P") (class "Default")
      (node (ref "C64") (pin "1") (pinfunction "1_1") (pintype "passive"))
      (node (ref "U15") (pin "46") (pinfunction "USB_SSRXP_46") (pintype "input"))
    )
    (net (code "13") (name "1.2VDC_A") (class "Default")
      (node (ref "C12") (pin "2") (pinfunction "2_2") (pintype "passive"))
      (node (ref "C125") (pin "1") (pinfunction "1_1") (pintype "passive"))
      (node (ref "C126") (pin "1") (pinfunction "1_1") (pintype "passive"))
      (node (ref "C14") (pin "2") (pinfunction "2_2") (pintype "passive"))
      (node (ref "C16") (pin "2") (pinfunction "2_2") (pintype "passive"))
      (node (ref "C18") (pin "2") (pinfunction "2_2") (pintype "passive"))
      (node (ref "C21") (pin "2") (pinfunction "2_2") (pintype "passive"))
      (node (ref "C23") (pin "2") (pinfunction "2_2") (pintype "passive"))
      (node (ref "L13") (pin "2") (pinfunction "2_2") (pintype "passive"))
      (node (ref "R44") (pin "1") (pinfunction "1_1") (pintype "passive"))
      (node (ref "U7") (pin "1") (pinfunction "VDD_1") (pintype "power_in"))
      (node (ref "U7") (pin "12") (pinfunction "VDD_12") (pintype "power_in"))
      (node (ref "U7") (pin "18") (pinfunction "VDD_18") (pintype "power_in"))
      (node (ref "U7") (pin "30") (pinfunction "VDD_30") (pintype "power_in"))
      (node (ref "U7") (pin "34") (pinfunction "VDD_34") (pintype "power_in"))
      (node (ref "U7") (pin "45") (pinfunction "VDD_45") (pintype "power_in"))
    )
    (net (code "14") (name "1.2VDC_B") (class "Default")
      (node (ref "C106") (pin "2") (pinfunction "2_2") (pintype "passive"))
      (node (ref "C107") (pin "2") (pinfunction "2_2") (pintype "passive"))
      (node (ref "C108") (pin "2") (pinfunction "2_2") (pintype "passive"))
      (node (ref "C109") (pin "2") (pinfunction "2_2") (pintype "passive"))
      (node (ref "C110") (pin "2") (pinfunction "2_2") (pintype "passive"))
      (node (ref "C111") (pin "2") (pinfunction "2_2") (pintype "passive"))
      (node (ref "C113") (pin "2") (pinfunction "2_2") (pintype "passive"))
      (node (ref "C115") (pin "2") (pinfunction "2_2") (pintype "passive"))
      (node (ref "C118") (pin "2") (pinfunction "2_2") (pintype "passive"))
      (node (ref "C120") (pin "2") (pinfunction "2_2") (pintype "passive"))
      (node (ref "C121") (pin "2") (pinfunction "2_2") (pintype "passive"))
      (node (ref "C13") (pin "2") (pinfunction "2_2") (pintype "passive"))
      (node (ref "C136") (pin "1") (pinfunction "1_1") (pintype "passive"))
      (node (ref "C137") (pin "1") (pinfunction "1_1") (pintype "passive"))
      (node (ref "C15") (pin "2") (pinfunction "2_2") (pintype "passive"))
      (node (ref "C17") (pin "2") (pinfunction "2_2") (pintype "passive"))
      (node (ref "C19") (pin "2") (pinfunction "2_2") (pintype "passive"))
      (node (ref "C22") (pin "2") (pinfunction "2_2") (pintype "passive"))
      (node (ref "C24") (pin "2") (pinfunction "2_2") (pintype "passive"))
      (node (ref "C27") (pin "2") (pinfunction "2_2") (pintype "passive"))
      (node (ref "C29") (pin "2") (pinfunction "2_2") (pintype "passive"))
      (node (ref "C31") (pin "2") (pinfunction "2_2") (pintype "passive"))
      (node (ref "C34") (pin "2") (pinfunction "2_2") (pintype "passive"))
      (node (ref "C36") (pin "2") (pinfunction "2_2") (pintype "passive"))
      (node (ref "L14") (pin "2") (pinfunction "2_2") (pintype "passive"))
      (node (ref "R49") (pin "1") (pinfunction "1_1") (pintype "passive"))
      (node (ref "U10") (pin "1") (pinfunction "VDD_1") (pintype "power_in"))
      (node (ref "U10") (pin "12") (pinfunction "VDD_12") (pintype "power_in"))
      (node (ref "U10") (pin "19") (pinfunction "VDD_19") (pintype "power_in"))
      (node (ref "U10") (pin "32") (pinfunction "VDD_32") (pintype "power_in"))
      (node (ref "U10") (pin "33") (pinfunction "VDD_33") (pintype "power_in"))
      (node (ref "U10") (pin "41") (pinfunction "VDD_41") (pintype "power_in"))
      (node (ref "U10") (pin "47") (pinfunction "VDD_47") (pintype "power_in"))
      (node (ref "U10") (pin "49") (pinfunction "VDD_49") (pintype "power_in"))
      (node (ref "U10") (pin "55") (pinfunction "VDD_55") (pintype "power_in"))
      (node (ref "U10") (pin "61") (pinfunction "VDD_61") (pintype "power_in"))
      (node (ref "U10") (pin "63") (pinfunction "VDD_63") (pintype "power_in"))
      (node (ref "U15") (pin "1") (pinfunction "VDD_1") (pintype "power_in"))
      (node (ref "U15") (pin "12") (pinfunction "VDD_12") (pintype "power_in"))
      (node (ref "U15") (pin "19") (pinfunction "VDD_19") (pintype "power_in"))
      (node (ref "U15") (pin "32") (pinfunction "VDD_32") (pintype "power_in"))
      (node (ref "U15") (pin "33") (pinfunction "VDD_33") (pintype "power_in"))
      (node (ref "U15") (pin "41") (pinfunction "VDD_41") (pintype "power_in"))
      (node (ref "U15") (pin "47") (pinfunction "VDD_47") (pintype "power_in"))
      (node (ref "U15") (pin "49") (pinfunction "VDD_49") (pintype "power_in"))
      (node (ref "U15") (pin "55") (pinfunction "VDD_55") (pintype "power_in"))
      (node (ref "U15") (pin "61") (pinfunction "VDD_61") (pintype "power_in"))
      (node (ref "U15") (pin "63") (pinfunction "VDD_63") (pintype "power_in"))
    )
    (net (code "15") (name "3v3_PER") (class "Default")
      (node (ref "C122") (pin "2") (pinfunction "2_2") (pintype "passive"))
      (node (ref "C127") (pin "2") (pinfunction "2_2") (pintype "passive"))
      (node (ref "C128") (pin "2") (pinfunction "2_2") (pintype "passive"))
      (node (ref "C129") (pin "2") (pinfunction "2_2") (pintype "passive"))
      (node (ref "C130") (pin "2") (pinfunction "2_2") (pintype "passive"))
      (node (ref "C131") (pin "2") (pinfunction "2_2") (pintype "passive"))
      (node (ref "C132") (pin "2") (pinfunction "2_2") (pintype "passive"))
      (node (ref "C162") (pin "1") (pinfunction "1_1") (pintype "passive"))
      (node (ref "C163") (pin "1") (pinfunction "1_1") (pintype "passive"))
      (node (ref "C26") (pin "2") (pinfunction "2_2") (pintype "passive"))
      (node (ref "C28") (pin "2") (pinfunction "2_2") (pintype "passive"))
      (node (ref "C30") (pin "2") (pinfunction "2_2") (pintype "passive"))
      (node (ref "C33") (pin "2") (pinfunction "2_2") (pintype "passive"))
      (node (ref "C35") (pin "2") (pinfunction "2_2") (pintype "passive"))
      (node (ref "C38") (pin "2") (pinfunction "2_2") (pintype "passive"))
      (node (ref "C39") (pin "2") (pinfunction "2_2") (pintype "passive"))
      (node (ref "C40") (pin "2") (pinfunction "2_2") (pintype "passive"))
      (node (ref "C41") (pin "2") (pinfunction "2_2") (pintype "passive"))
      (node (ref "C42") (pin "2") (pinfunction "2_2") (pintype "passive"))
      (node (ref "C43") (pin "2") (pinfunction "2_2") (pintype "passive"))
      (node (ref "C45") (pin "2") (pinfunction "2_2") (pintype "passive"))
      (node (ref "C46") (pin "2") (pinfunction "2_2") (pintype "passive"))
      (node (ref "C49") (pin "2") (pinfunction "2_2") (pintype "passive"))
      (node (ref "C51") (pin "2") (pinfunction "2_2") (pintype "passive"))
      (node (ref "R109") (pin "1") (pinfunction "1_1") (pintype "passive"))
      (node (ref "R110") (pin "1") (pinfunction "1_1") (pintype "passive"))
      (node (ref "R111") (pin "1") (pinfunction "1_1") (pintype "passive"))
      (node (ref "R112") (pin "1") (pinfunction "1_1") (pintype "passive"))
      (node (ref "R35") (pin "1") (pinfunction "1_1") (pintype "passive"))
      (node (ref "R36") (pin "1") (pinfunction "1_1") (pintype "passive"))
      (node (ref "R40") (pin "2") (pinfunction "2_2") (pintype "passive"))
      (node (ref "R41") (pin "2") (pinfunction "2_2") (pintype "passive"))
      (node (ref "R42") (pin "1") (pinfunction "1_1") (pintype "passive"))
      (node (ref "R43") (pin "1") (pinfunction "1_1") (pintype "passive"))
      (node (ref "R51") (pin "2") (pinfunction "2_2") (pintype "passive"))
      (node (ref "R52") (pin "2") (pinfunction "2_2") (pintype "passive"))
      (node (ref "R62") (pin "2") (pinfunction "2_2") (pintype "passive"))
      (node (ref "R71") (pin "1") (pinfunction "1_1") (pintype "passive"))
      (node (ref "U10") (pin "24") (pinfunction "VDD33_24") (pintype "power_in"))
      (node (ref "U10") (pin "34") (pinfunction "VDDA33_34") (pintype "power_in"))
      (node (ref "U10") (pin "40") (pinfunction "VDDA33_40") (pintype "power_in"))
      (node (ref "U10") (pin "48") (pinfunction "VDDA33_48") (pintype "power_in"))
      (node (ref "U10") (pin "51") (pinfunction "VDD33_51") (pintype "power_in"))
      (node (ref "U10") (pin "62") (pinfunction "VDDA33_62") (pintype "power_in"))
      (node (ref "U10") (pin "7") (pinfunction "VDD33_7") (pintype "power_in"))
      (node (ref "U15") (pin "24") (pinfunction "VDD33_24") (pintype "power_in"))
      (node (ref "U15") (pin "34") (pinfunction "VDDA33_34") (pintype "power_in"))
      (node (ref "U15") (pin "40") (pinfunction "VDDA33_40") (pintype "power_in"))
      (node (ref "U15") (pin "48") (pinfunction "VDDA33_48") (pintype "power_in"))
      (node (ref "U15") (pin "51") (pinfunction "VDD33_51") (pintype "power_in"))
      (node (ref "U15") (pin "62") (pinfunction "VDDA33_62") (pintype "power_in"))
      (node (ref "U15") (pin "7") (pinfunction "VDD33_7") (pintype "power_in"))
      (node (ref "U21") (pin "8") (pinfunction "VDD_8") (pintype "power_in"))
      (node (ref "U22") (pin "8") (pinfunction "VDD_8") (pintype "power_in"))
      (node (ref "U25") (pin "2") (pinfunction "VDD_2") (pintype "power_in"))
      (node (ref "U7") (pin "13") (pinfunction "VDD33_13") (pintype "power_in"))
      (node (ref "U7") (pin "23") (pinfunction "VDD33_23") (pintype "power_in"))
      (node (ref "U7") (pin "25") (pinfunction "VDD33_25") (pintype "power_in"))
      (node (ref "U7") (pin "33") (pinfunction "VDD33_33") (pintype "power_in"))
      (node (ref "U7") (pin "37") (pinfunction "VDD33_37") (pintype "power_in"))
      (node (ref "U7") (pin "40") (pinfunction "VDD33_40") (pintype "power_in"))
      (node (ref "U7") (pin "48") (pinfunction "VDD33_48") (pintype "power_in"))
      (node (ref "U7") (pin "7") (pinfunction "VDD33_7") (pintype "power_in"))
    )
    (net (code "16") (name "5v_PER") (class "Default")
      (node (ref "C10") (pin "1") (pinfunction "1_1") (pintype "passive"))
      (node (ref "C123") (pin "1") (pinfunction "1_1") (pintype "passive"))
      (node (ref "C124") (pin "1") (pinfunction "1_1") (pintype "passive"))
      (node (ref "C134") (pin "1") (pinfunction "1_1") (pintype "passive"))
      (node (ref "C135") (pin "1") (pinfunction "1_1") (pintype "passive"))
      (node (ref "C78") (pin "1") (pinfunction "1_1") (pintype "passive"))
      (node (ref "C86") (pin "1") (pinfunction "1_1") (pintype "passive"))
      (node (ref "C88") (pin "1") (pinfunction "1_1") (pintype "passive"))
      (node (ref "FB5") (pin "1") (pinfunction "1_1") (pintype "passive"))
      (node (ref "FB7") (pin "1") (pinfunction "1_1") (pintype "passive"))
      (node (ref "R13") (pin "1") (pinfunction "1_1") (pintype "passive"))
      (node (ref "R37") (pin "1") (pinfunction "1_1") (pintype "passive"))
      (node (ref "R46") (pin "1") (pinfunction "1_1") (pintype "passive"))
      (node (ref "U16") (pin "2") (pinfunction "EN_2") (pintype "passive"))
      (node (ref "U16") (pin "3") (pinfunction "VIN_3") (pintype "passive"))
      (node (ref "U17") (pin "2") (pinfunction "EN_2") (pintype "passive"))
      (node (ref "U17") (pin "3") (pinfunction "VIN_3") (pintype "passive"))
    )
    (net (code "17") (name "12v_PER") (class "Default")
      (node (ref "C6") (pin "1") (pinfunction "1_1") (pintype "passive"))
      (node (ref "C7") (pin "1") (pinfunction "1_1") (pintype "passive"))
      (node (ref "C8") (pin "1") (pinfunction "1_1") (pintype "passive"))
      (node (ref "C9") (pin "1") (pinfunction "1_1") (pintype "passive"))
      (node (ref "FB6") (pin "1") (pinfunction "1_1") (pintype "passive"))
      (node (ref "FB8") (pin "1") (pinfunction "1_1") (pintype "passive"))
    )
    (net (code "18") (name "GND") (class "Default")
      (node (ref "C10") (pin "2") (pinfunction "2_2") (pintype "passive"))
      (node (ref "C106") (pin "1") (pinfunction "1_1") (pintype "passive"))
      (node (ref "C107") (pin "1") (pinfunction "1_1") (pintype "passive"))
      (node (ref "C108") (pin "1") (pinfunction "1_1") (pintype "passive"))
      (node (ref "C109") (pin "1") (pinfunction "1_1") (pintype "passive"))
      (node (ref "C11") (pin "1") (pinfunction "1_1") (pintype "passive"))
      (node (ref "C110") (pin "1") (pinfunction "1_1") (pintype "passive"))
      (node (ref "C111") (pin "1") (pinfunction "1_1") (pintype "passive"))
      (node (ref "C113") (pin "1") (pinfunction "1_1") (pintype "passive"))
      (node (ref "C115") (pin "1") (pinfunction "1_1") (pintype "passive"))
      (node (ref "C118") (pin "1") (pinfunction "1_1") (pintype "passive"))
      (node (ref "C12") (pin "1") (pinfunction "1_1") (pintype "passive"))
      (node (ref "C120") (pin "1") (pinfunction "1_1") (pintype "passive"))
      (node (ref "C121") (pin "1") (pinfunction "1_1") (pintype "passive"))
      (node (ref "C122") (pin "1") (pinfunction "1_1") (pintype "passive"))
      (node (ref "C123") (pin "2") (pinfunction "2_2") (pintype "passive"))
      (node (ref "C124") (pin "2") (pinfunction "2_2") (pintype "passive"))
      (node (ref "C125") (pin "2") (pinfunction "2_2") (pintype "passive"))
      (node (ref "C126") (pin "2") (pinfunction "2_2") (pintype "passive"))
      (node (ref "C127") (pin "1") (pinfunction "1_1") (pintype "passive"))
      (node (ref "C128") (pin "1") (pinfunction "1_1") (pintype "passive"))
      (node (ref "C129") (pin "1") (pinfunction "1_1") (pintype "passive"))
      (node (ref "C13") (pin "1") (pinfunction "1_1") (pintype "passive"))
      (node (ref "C130") (pin "1") (pinfunction "1_1") (pintype "passive"))
      (node (ref "C131") (pin "1") (pinfunction "1_1") (pintype "passive"))
      (node (ref "C132") (pin "1") (pinfunction "1_1") (pintype "passive"))
      (node (ref "C134") (pin "2") (pinfunction "2_2") (pintype "passive"))
      (node (ref "C135") (pin "2") (pinfunction "2_2") (pintype "passive"))
      (node (ref "C136") (pin "2") (pinfunction "2_2") (pintype "passive"))
      (node (ref "C137") (pin "2") (pinfunction "2_2") (pintype "passive"))
      (node (ref "C14") (pin "1") (pinfunction "1_1") (pintype "passive"))
      (node (ref "C15") (pin "1") (pinfunction "1_1") (pintype "passive"))
      (node (ref "C16") (pin "1") (pinfunction "1_1") (pintype "passive"))
      (node (ref "C162") (pin "2") (pinfunction "2_2") (pintype "passive"))
      (node (ref "C163") (pin "2") (pinfunction "2_2") (pintype "passive"))
      (node (ref "C17") (pin "1") (pinfunction "1_1") (pintype "passive"))
      (node (ref "C172") (pin "2") (pinfunction "2_2") (pintype "passive"))
      (node (ref "C173") (pin "1") (pinfunction "1_1") (pintype "passive"))
      (node (ref "C18") (pin "1") (pinfunction "1_1") (pintype "passive"))
      (node (ref "C19") (pin "1") (pinfunction "1_1") (pintype "passive"))
      (node (ref "C21") (pin "1") (pinfunction "1_1") (pintype "passive"))
      (node (ref "C22") (pin "1") (pinfunction "1_1") (pintype "passive"))
      (node (ref "C23") (pin "1") (pinfunction "1_1") (pintype "passive"))
      (node (ref "C24") (pin "1") (pinfunction "1_1") (pintype "passive"))
      (node (ref "C26") (pin "1") (pinfunction "1_1") (pintype "passive"))
      (node (ref "C27") (pin "1") (pinfunction "1_1") (pintype "passive"))
      (node (ref "C28") (pin "1") (pinfunction "1_1") (pintype "passive"))
      (node (ref "C29") (pin "1") (pinfunction "1_1") (pintype "passive"))
      (node (ref "C30") (pin "1") (pinfunction "1_1") (pintype "passive"))
      (node (ref "C31") (pin "1") (pinfunction "1_1") (pintype "passive"))
      (node (ref "C33") (pin "1") (pinfunction "1_1") (pintype "passive"))
      (node (ref "C34") (pin "1") (pinfunction "1_1") (pintype "passive"))
      (node (ref "C35") (pin "1") (pinfunction "1_1") (pintype "passive"))
      (node (ref "C36") (pin "1") (pinfunction "1_1") (pintype "passive"))
      (node (ref "C38") (pin "1") (pinfunction "1_1") (pintype "passive"))
      (node (ref "C39") (pin "1") (pinfunction "1_1") (pintype "passive"))
      (node (ref "C40") (pin "1") (pinfunction "1_1") (pintype "passive"))
      (node (ref "C41") (pin "1") (pinfunction "1_1") (pintype "passive"))
      (node (ref "C42") (pin "1") (pinfunction "1_1") (pintype "passive"))
      (node (ref "C43") (pin "1") (pinfunction "1_1") (pintype "passive"))
      (node (ref "C45") (pin "1") (pinfunction "1_1") (pintype "passive"))
      (node (ref "C46") (pin "1") (pinfunction "1_1") (pintype "passive"))
      (node (ref "C49") (pin "1") (pinfunction "1_1") (pintype "passive"))
      (node (ref "C51") (pin "1") (pinfunction "1_1") (pintype "passive"))
      (node (ref "C6") (pin "2") (pinfunction "2_2") (pintype "passive"))
      (node (ref "C66") (pin "1") (pinfunction "1_1") (pintype "passive"))
      (node (ref "C67") (pin "1") (pinfunction "1_1") (pintype "passive"))
      (node (ref "C7") (pin "2") (pinfunction "2_2") (pintype "passive"))
      (node (ref "C78") (pin "2") (pinfunction "2_2") (pintype "passive"))
      (node (ref "C8") (pin "2") (pinfunction "2_2") (pintype "passive"))
      (node (ref "C86") (pin "2") (pinfunction "2_2") (pintype "passive"))
      (node (ref "C88") (pin "2") (pinfunction "2_2") (pintype "passive"))
      (node (ref "C9") (pin "2") (pinfunction "2_2") (pintype "passive"))
      (node (ref "M1") (pin "2") (pinfunction "2_2") (pintype "passive"))
      (node (ref "M1") (pin "3") (pinfunction "3_3") (pintype "passive"))
      (node (ref "M2") (pin "2") (pinfunction "2_2") (pintype "passive"))
      (node (ref "M2") (pin "3") (pinfunction "3_3") (pintype "passive"))
      (node (ref "R11") (pin "1") (pinfunction "1_1") (pintype "passive"))
      (node (ref "R12") (pin "1") (pinfunction "1_1") (pintype "passive"))
      (node (ref "R14") (pin "1") (pinfunction "1_1") (pintype "passive"))
      (node (ref "R15") (pin "1") (pinfunction "1_1") (pintype "passive"))
      (node (ref "R16") (pin "1") (pinfunction "1_1") (pintype "passive"))
      (node (ref "R38") (pin "1") (pinfunction "1_1") (pintype "passive"))
      (node (ref "R45") (pin "1") (pinfunction "1_1") (pintype "passive"))
      (node (ref "R47") (pin "1") (pinfunction "1_1") (pintype "passive"))
      (node (ref "R50") (pin "1") (pinfunction "1_1") (pintype "passive"))
      (node (ref "S1") (pin "1") (pinfunction "1_1") (pintype "passive"))
      (node (ref "S1") (pin "4") (pinfunction "4_4") (pintype "passive"))
      (node (ref "S1") (pin "7") (pinfunction "7_7") (pintype "passive"))
      (node (ref "S2") (pin "1") (pinfunction "1_1") (pintype "passive"))
      (node (ref "S2") (pin "4") (pinfunction "4_4") (pintype "passive"))
      (node (ref "S2") (pin "7") (pinfunction "7_7") (pintype "passive"))
      (node (ref "U10") (pin "44") (pinfunction "VSS_44") (pintype "power_in"))
      (node (ref "U10") (pin "58") (pinfunction "VSS_58") (pintype "power_in"))
      (node (ref "U10") (pin "65") (pinfunction "EXP_VSS_65") (pintype "power_in"))
      (node (ref "U15") (pin "44") (pinfunction "VSS_44") (pintype "power_in"))
      (node (ref "U15") (pin "58") (pinfunction "VSS_58") (pintype "power_in"))
      (node (ref "U15") (pin "65") (pinfunction "EXP_VSS_65") (pintype "power_in"))
      (node (ref "U16") (pin "4") (pinfunction "GND_4") (pintype "power_in"))
      (node (ref "U17") (pin "4") (pinfunction "GND_4") (pintype "power_in"))
      (node (ref "U21") (pin "4") (pinfunction "VSS_4") (pintype "power_in"))
      (node (ref "U22") (pin "4") (pinfunction "VSS_4") (pintype "power_in"))
      (node (ref "U25") (pin "3") (pinfunction "GND_3") (pintype "power_in"))
      (node (ref "U26") (pin "3") (pinfunction "3_3") (pintype "passive"))
      (node (ref "U7") (pin "49") (pinfunction "GND_49") (pintype "power_in"))
      (node (ref "Y2") (pin "2") (pinfunction "GND_2") (pintype "power_in"))
      (node (ref "Y2") (pin "4") (pinfunction "GND_4") (pintype "power_in"))
      (node (ref "Y4") (pin "2") (pinfunction "GND_2") (pintype "power_in"))
      (node (ref "Y4") (pin "4") (pinfunction "GND_4") (pintype "power_in"))
      (node (ref "Y5") (pin "2") (pinfunction "GND_2") (pintype "power_in"))
      (node (ref "Y5") (pin "4") (pinfunction "GND_4") (pintype "power_in"))
    )
    (net (code "19") (name "Net-(FB5-Pad2)") (class "Default")
      (node (ref "FB5") (pin "2") (pinfunction "2_2") (pintype "passive"))
      (node (ref "M1") (pin "1") (pinfunction "1_1") (pintype "passive"))
    )
    (net (code "20") (name "Net-(FB6-Pad2)") (class "Default")
      (node (ref "FB6") (pin "2") (pinfunction "2_2") (pintype "passive"))
      (node (ref "M1") (pin "4") (pinfunction "4_4") (pintype "passive"))
    )
    (net (code "21") (name "Net-(FB7-Pad2)") (class "Default")
      (node (ref "FB7") (pin "2") (pinfunction "2_2") (pintype "passive"))
      (node (ref "M2") (pin "1") (pinfunction "1_1") (pintype "passive"))
    )
    (net (code "22") (name "Net-(FB8-Pad2)") (class "Default")
      (node (ref "FB8") (pin "2") (pinfunction "2_2") (pintype "passive"))
      (node (ref "M2") (pin "4") (pinfunction "4_4") (pintype "passive"))
    )
    (net (code "23") (name "Net-(LED2-Anode)") (class "Default")
      (node (ref "LED2") (pin "2") (pinfunction "Anode_2") (pintype "passive"))
      (node (ref "R40") (pin "1") (pinfunction "1_1") (pintype "passive"))
    )
    (net (code "24") (name "Net-(LED2-Cathode)") (class "Default")
      (node (ref "LED2") (pin "1") (pinfunction "Cathode_1") (pintype "passive"))
      (node (ref "U10") (pin "2") (pinfunction "PWM0_2") (pintype "output"))
    )
    (net (code "25") (name "Net-(LED3-Anode)") (class "Default")
      (node (ref "LED3") (pin "2") (pinfunction "Anode_2") (pintype "passive"))
      (node (ref "R41") (pin "1") (pinfunction "1_1") (pintype "passive"))
    )
    (net (code "26") (name "Net-(LED3-Cathode)") (class "Default")
      (node (ref "LED3") (pin "1") (pinfunction "Cathode_1") (pintype "passive"))
      (node (ref "U10") (pin "3") (pinfunction "PWM1_3") (pintype "output"))
    )
    (net (code "27") (name "Net-(LED4-Anode)") (class "Default")
      (node (ref "LED4") (pin "2") (pinfunction "Anode_2") (pintype "passive"))
      (node (ref "R51") (pin "1") (pinfunction "1_1") (pintype "passive"))
    )
    (net (code "28") (name "Net-(LED4-Cathode)") (class "Default")
      (node (ref "LED4") (pin "1") (pinfunction "Cathode_1") (pintype "passive"))
      (node (ref "U15") (pin "2") (pinfunction "PWM0_2") (pintype "output"))
    )
    (net (code "29") (name "Net-(LED5-Anode)") (class "Default")
      (node (ref "LED5") (pin "2") (pinfunction "Anode_2") (pintype "passive"))
      (node (ref "R52") (pin "1") (pinfunction "1_1") (pintype "passive"))
    )
    (net (code "30") (name "Net-(LED5-Cathode)") (class "Default")
      (node (ref "LED5") (pin "1") (pinfunction "Cathode_1") (pintype "passive"))
      (node (ref "U15") (pin "3") (pinfunction "PWM1_3") (pintype "output"))
    )
    (net (code "31") (name "Net-(R57-Pad1)") (class "Default")
      (node (ref "R57") (pin "1") (pinfunction "1_1") (pintype "passive"))
      (node (ref "U26") (pin "4") (pinfunction "4_4") (pintype "passive"))
    )
    (net (code "32") (name "Net-(R62-Pad1)") (class "Default")
      (node (ref "R62") (pin "1") (pinfunction "1_1") (pintype "passive"))
      (node (ref "U26") (pin "1") (pinfunction "1_1") (pintype "passive"))
    )
    (net (code "33") (name "Net-(U7-GANGED{slash}SMBA2{slash}HS_UP)") (class "Default")
      (node (ref "R15") (pin "2") (pinfunction "2_2") (pintype "passive"))
      (node (ref "U7") (pin "35") (pinfunction "GANGED/SMBA2/HS_UP_35") (pintype "input"))
    )
    (net (code "34") (name "Net-(U7-GRSTZ)") (class "Default")
      (node (ref "C11") (pin "2") (pinfunction "2_2") (pintype "passive"))
      (node (ref "U7") (pin "11") (pinfunction "GRSTZ_11") (pintype "input"))
    )
    (net (code "35") (name "Net-(U7-PWRCRL_POL{slash}SS_DN1)") (class "Default")
      (node (ref "R14") (pin "2") (pinfunction "2_2") (pintype "passive"))
      (node (ref "U7") (pin "21") (pinfunction "PWRCRL_POL/SS_DN1_21") (pintype "bidirectional"))
    )
    (net (code "36") (name "Net-(U7-TEST)") (class "Default")
      (node (ref "R16") (pin "2") (pinfunction "2_2") (pintype "passive"))
      (node (ref "U7") (pin "10") (pinfunction "TEST_10") (pintype "input"))
    )
    (net (code "37") (name "Net-(U7-USB_R1)") (class "Default")
      (node (ref "R11") (pin "2") (pinfunction "2_2") (pintype "passive"))
      (node (ref "U7") (pin "24") (pinfunction "USB_R1_24") (pintype "input"))
    )
    (net (code "38") (name "Net-(U7-USB_SSRXM_DN1)") (class "Default")
      (node (ref "C37") (pin "1") (pinfunction "1_1") (pintype "passive"))
      (node (ref "U7") (pin "47") (pinfunction "USB_SSRXM_DN1_47") (pintype "input"))
    )
    (net (code "39") (name "Net-(U7-USB_SSRXM_DN2)") (class "Default")
      (node (ref "C47") (pin "1") (pinfunction "1_1") (pintype "passive"))
      (node (ref "U7") (pin "20") (pinfunction "USB_SSRXM_DN2_20") (pintype "input"))
    )
    (net (code "40") (name "Net-(U7-USB_SSRXP_DN1)") (class "Default")
      (node (ref "C32") (pin "1") (pinfunction "1_1") (pintype "passive"))
      (node (ref "U7") (pin "46") (pinfunction "USB_SSRXP_DN1_46") (pintype "input"))
    )
    (net (code "41") (name "Net-(U7-USB_SSRXP_DN2)") (class "Default")
      (node (ref "C44") (pin "1") (pinfunction "1_1") (pintype "passive"))
      (node (ref "U7") (pin "19") (pinfunction "USB_SSRXP_DN2_19") (pintype "input"))
    )
    (net (code "42") (name "Net-(U7-USB_SSTXM_DN1)") (class "Default")
      (node (ref "C63") (pin "2") (pinfunction "2_2") (pintype "passive"))
      (node (ref "U7") (pin "44") (pinfunction "USB_SSTXM_DN1_44") (pintype "output"))
    )
    (net (code "43") (name "Net-(U7-USB_SSTXM_DN2)") (class "Default")
      (node (ref "C65") (pin "2") (pinfunction "2_2") (pintype "passive"))
      (node (ref "U7") (pin "17") (pinfunction "USB_SSTXM_DN2_17") (pintype "output"))
    )
    (net (code "44") (name "Net-(U7-USB_SSTXM_UP)") (class "Default")
      (node (ref "C50") (pin "2") (pinfunction "2_2") (pintype "passive"))
      (node (ref "U7") (pin "28") (pinfunction "USB_SSTXM_UP_28") (pintype "output"))
    )
    (net (code "45") (name "Net-(U7-USB_SSTXP_DN1)") (class "Default")
      (node (ref "C52") (pin "2") (pinfunction "2_2") (pintype "passive"))
      (node (ref "U7") (pin "43") (pinfunction "USB_SSTXP_DN1_43") (pintype "output"))
    )
    (net (code "46") (name "Net-(U7-USB_SSTXP_DN2)") (class "Default")
      (node (ref "C64") (pin "2") (pinfunction "2_2") (pintype "passive"))
      (node (ref "U7") (pin "16") (pinfunction "USB_SSTXP_DN2_16") (pintype "output"))
    )
    (net (code "47") (name "Net-(U7-USB_SSTXP_UP)") (class "Default")
      (node (ref "C48") (pin "2") (pinfunction "2_2") (pintype "passive"))
      (node (ref "U7") (pin "29") (pinfunction "USB_SSTXP_UP_29") (pintype "output"))
    )
    (net (code "48") (name "Net-(U7-USB_VBUS)") (class "Default")
      (node (ref "R12") (pin "2") (pinfunction "2_2") (pintype "passive"))
      (node (ref "R13") (pin "2") (pinfunction "2_2") (pintype "passive"))
      (node (ref "U7") (pin "9") (pinfunction "USB_VBUS_9") (pintype "input"))
    )
    (net (code "49") (name "Net-(U7-XI)") (class "Default")
      (node (ref "C66") (pin "2") (pinfunction "2_2") (pintype "passive"))
      (node (ref "R17") (pin "1") (pinfunction "1_1") (pintype "passive"))
      (node (ref "U7") (pin "38") (pinfunction "XI_38") (pintype "input"))
      (node (ref "Y2") (pin "3") (pintype "passive"))
    )
    (net (code "50") (name "Net-(U7-XO)") (class "Default")
      (node (ref "C67") (pin "2") (pinfunction "2_2") (pintype "passive"))
      (node (ref "R17") (pin "2") (pinfunction "2_2") (pintype "passive"))
      (node (ref "U7") (pin "39") (pinfunction "XO_39") (pintype "output"))
      (node (ref "Y2") (pin "1") (pintype "passive"))
    )
    (net (code "51") (name "Net-(U10-FREQSEL0)") (class "Default")
      (node (ref "R35") (pin "2") (pinfunction "2_2") (pintype "passive"))
      (node (ref "U10") (pin "30") (pinfunction "FREQSEL0_30") (pintype "input"))
    )
    (net (code "52") (name "Net-(U10-FREQSEL1)") (class "Default")
      (node (ref "R36") (pin "2") (pinfunction "2_2") (pintype "passive"))
      (node (ref "U10") (pin "31") (pinfunction "FREQSEL1_31") (pintype "input"))
    )
    (net (code "53") (name "Net-(U10-SATA_RXM)") (class "Default")
      (node (ref "C104") (pin "1") (pinfunction "1_1") (pintype "passive"))
      (node (ref "U10") (pin "59") (pinfunction "SATA_RXM_59") (pintype "input"))
    )
    (net (code "54") (name "Net-(U10-SATA_RXP)") (class "Default")
      (node (ref "C102") (pin "1") (pinfunction "1_1") (pintype "passive"))
      (node (ref "U10") (pin "60") (pinfunction "SATA_RXP_60") (pintype "input"))
    )
    (net (code "55") (name "Net-(U10-SATA_TXM)") (class "Default")
      (node (ref "C105") (pin "1") (pinfunction "1_1") (pintype "passive"))
      (node (ref "U10") (pin "56") (pinfunction "SATA_TXM_56") (pintype "output"))
    )
    (net (code "56") (name "Net-(U10-SATA_TXP)") (class "Default")
      (node (ref "C103") (pin "1") (pinfunction "1_1") (pintype "passive"))
      (node (ref "U10") (pin "57") (pinfunction "SATA_TXP_57") (pintype "output"))
    )
    (net (code "57") (name "Net-(U10-USB_R1)") (class "Default")
      (node (ref "R39") (pin "2") (pinfunction "2_2") (pintype "passive"))
      (node (ref "U10") (pin "38") (pinfunction "USB_R1_38") (pintype "output"))
    )
    (net (code "58") (name "Net-(U10-USB_R1RTN)") (class "Default")
      (node (ref "R39") (pin "1") (pinfunction "1_1") (pintype "passive"))
      (node (ref "U10") (pin "39") (pinfunction "USB_R1RTN_39") (pintype "input"))
    )
    (net (code "59") (name "Net-(U10-USB_VBUS)") (class "Default")
      (node (ref "R37") (pin "2") (pinfunction "2_2") (pintype "passive"))
      (node (ref "R38") (pin "2") (pinfunction "2_2") (pintype "passive"))
      (node (ref "U10") (pin "50") (pinfunction "USB_VBUS_50") (pintype "input"))
    )
    (net (code "60") (name "Net-(U10-XI)") (class "Default")
      (node (ref "U10") (pin "52") (pinfunction "XI_52") (pintype "input"))
      (node (ref "Y4") (pin "3") (pintype "passive"))
    )
    (net (code "61") (name "Net-(U10-XO)") (class "Default")
      (node (ref "U10") (pin "54") (pinfunction "XO_54") (pintype "output"))
      (node (ref "Y4") (pin "1") (pintype "passive"))
    )
    (net (code "62") (name "Net-(U15-FREQSEL0)") (class "Default")
      (node (ref "R42") (pin "2") (pinfunction "2_2") (pintype "passive"))
      (node (ref "U15") (pin "30") (pinfunction "FREQSEL0_30") (pintype "input"))
    )
    (net (code "63") (name "Net-(U15-FREQSEL1)") (class "Default")
      (node (ref "R43") (pin "2") (pinfunction "2_2") (pintype "passive"))
      (node (ref "U15") (pin "31") (pinfunction "FREQSEL1_31") (pintype "input"))
    )
    (net (code "64") (name "Net-(U15-SATA_RXM)") (class "Default")
      (node (ref "C117") (pin "1") (pinfunction "1_1") (pintype "passive"))
      (node (ref "U15") (pin "59") (pinfunction "SATA_RXM_59") (pintype "input"))
    )
    (net (code "65") (name "Net-(U15-SATA_RXP)") (class "Default")
      (node (ref "C112") (pin "1") (pinfunction "1_1") (pintype "passive"))
      (node (ref "U15") (pin "60") (pinfunction "SATA_RXP_60") (pintype "input"))
    )
    (net (code "66") (name "Net-(U15-SATA_TXM)") (class "Default")
      (node (ref "C119") (pin "1") (pinfunction "1_1") (pintype "passive"))
      (node (ref "U15") (pin "56") (pinfunction "SATA_TXM_56") (pintype "output"))
    )
    (net (code "67") (name "Net-(U15-SATA_TXP)") (class "Default")
      (node (ref "C114") (pin "1") (pinfunction "1_1") (pintype "passive"))
      (node (ref "U15") (pin "57") (pinfunction "SATA_TXP_57") (pintype "output"))
    )
    (net (code "68") (name "Net-(U15-USB_R1)") (class "Default")
      (node (ref "R48") (pin "2") (pinfunction "2_2") (pintype "passive"))
      (node (ref "U15") (pin "38") (pinfunction "USB_R1_38") (pintype "output"))
    )
    (net (code "69") (name "Net-(U15-USB_R1RTN)") (class "Default")
      (node (ref "R48") (pin "1") (pinfunction "1_1") (pintype "passive"))
      (node (ref "U15") (pin "39") (pinfunction "USB_R1RTN_39") (pintype "input"))
    )
    (net (code "70") (name "Net-(U15-USB_VBUS)") (class "Default")
      (node (ref "R46") (pin "2") (pinfunction "2_2") (pintype "passive"))
      (node (ref "R47") (pin "2") (pinfunction "2_2") (pintype "passive"))
      (node (ref "U15") (pin "50") (pinfunction "USB_VBUS_50") (pintype "input"))
    )
    (net (code "71") (name "Net-(U15-XI)") (class "Default")
      (node (ref "U15") (pin "52") (pinfunction "XI_52") (pintype "input"))
      (node (ref "Y5") (pin "3") (pintype "passive"))
    )
    (net (code "72") (name "Net-(U15-XO)") (class "Default")
      (node (ref "U15") (pin "54") (pinfunction "XO_54") (pintype "output"))
      (node (ref "Y5") (pin "1") (pintype "passive"))
    )
    (net (code "73") (name "Net-(U16-BST)") (class "Default")
      (node (ref "C116") (pin "1") (pinfunction "1_1") (pintype "passive"))
      (node (ref "U16") (pin "6") (pinfunction "BST_6") (pintype "passive"))
    )
    (net (code "74") (name "Net-(U16-FB)") (class "Default")
      (node (ref "R44") (pin "2") (pinfunction "2_2") (pintype "passive"))
      (node (ref "R45") (pin "2") (pinfunction "2_2") (pintype "passive"))
      (node (ref "U16") (pin "1") (pinfunction "FB_1") (pintype "passive"))
    )
    (net (code "75") (name "Net-(U16-SW)") (class "Default")
      (node (ref "C116") (pin "2") (pinfunction "2_2") (pintype "passive"))
      (node (ref "L13") (pin "1") (pinfunction "1_1") (pintype "passive"))
      (node (ref "U16") (pin "5") (pinfunction "SW_5") (pintype "passive"))
    )
    (net (code "76") (name "Net-(U17-BST)") (class "Default")
      (node (ref "C133") (pin "1") (pinfunction "1_1") (pintype "passive"))
      (node (ref "U17") (pin "6") (pinfunction "BST_6") (pintype "passive"))
    )
    (net (code "77") (name "Net-(U17-FB)") (class "Default")
      (node (ref "R49") (pin "2") (pinfunction "2_2") (pintype "passive"))
      (node (ref "R50") (pin "2") (pinfunction "2_2") (pintype "passive"))
      (node (ref "U17") (pin "1") (pinfunction "FB_1") (pintype "passive"))
    )
    (net (code "78") (name "Net-(U17-SW)") (class "Default")
      (node (ref "C133") (pin "2") (pinfunction "2_2") (pintype "passive"))
      (node (ref "L14") (pin "1") (pinfunction "1_1") (pintype "passive"))
      (node (ref "U17") (pin "5") (pinfunction "SW_5") (pintype "passive"))
    )
    (net (code "79") (name "Net-(U21-*HOLD)") (class "Default")
      (node (ref "R110") (pin "2") (pinfunction "2_2") (pintype "passive"))
      (node (ref "U21") (pin "7") (pinfunction "*HOLD_7") (pintype "passive"))
    )
    (net (code "80") (name "Net-(U21-*WP)") (class "Default")
      (node (ref "R109") (pin "2") (pinfunction "2_2") (pintype "passive"))
      (node (ref "U21") (pin "3") (pinfunction "*WP_3") (pintype "passive"))
    )
    (net (code "81") (name "Net-(U22-*HOLD)") (class "Default")
      (node (ref "R112") (pin "2") (pinfunction "2_2") (pintype "passive"))
      (node (ref "U22") (pin "7") (pinfunction "*HOLD_7") (pintype "passive"))
    )
    (net (code "82") (name "Net-(U22-*WP)") (class "Default")
      (node (ref "R111") (pin "2") (pinfunction "2_2") (pintype "passive"))
      (node (ref "U22") (pin "3") (pinfunction "*WP_3") (pintype "passive"))
    )
    (net (code "83") (name "Net-(U25-CT)") (class "Default")
      (node (ref "C172") (pin "1") (pinfunction "1_1") (pintype "passive"))
      (node (ref "U25") (pin "5") (pinfunction "CT_5") (pintype "input"))
    )
    (net (code "84") (name "Net-(U25-RST_N)") (class "Default")
      (node (ref "U25") (pin "1") (pinfunction "RST_N_1") (pintype "open_collector"))
      (node (ref "U26") (pin "2") (pinfunction "2_2") (pintype "passive"))
    )
    (net (code "85") (name "S1_RX_N") (class "Default")
      (node (ref "C104") (pin "2") (pinfunction "2_2") (pintype "passive"))
      (node (ref "S1") (pin "5") (pinfunction "5_5") (pintype "passive"))
    )
    (net (code "86") (name "S1_RX_P") (class "Default")
      (node (ref "C102") (pin "2") (pinfunction "2_2") (pintype "passive"))
      (node (ref "S1") (pin "6") (pinfunction "6_6") (pintype "passive"))
    )
    (net (code "87") (name "S1_TX_N") (class "Default")
      (node (ref "C105") (pin "2") (pinfunction "2_2") (pintype "passive"))
      (node (ref "S1") (pin "3") (pinfunction "3_3") (pintype "passive"))
    )
    (net (code "88") (name "S1_TX_P") (class "Default")
      (node (ref "C103") (pin "2") (pinfunction "2_2") (pintype "passive"))
      (node (ref "S1") (pin "2") (pinfunction "2_2") (pintype "passive"))
    )
    (net (code "89") (name "S2_RX_N") (class "Default")
      (node (ref "C117") (pin "2") (pinfunction "2_2") (pintype "passive"))
      (node (ref "S2") (pin "5") (pinfunction "5_5") (pintype "passive"))
    )
    (net (code "90") (name "S2_RX_P") (class "Default")
      (node (ref "C112") (pin "2") (pinfunction "2_2") (pintype "passive"))
      (node (ref "S2") (pin "6") (pinfunction "6_6") (pintype "passive"))
    )
    (net (code "91") (name "S2_TX_N") (class "Default")
      (node (ref "C119") (pin "2") (pinfunction "2_2") (pintype "passive"))
      (node (ref "S2") (pin "3") (pinfunction "3_3") (pintype "passive"))
    )
    (net (code "92") (name "S2_TX_P") (class "Default")
      (node (ref "C114") (pin "2") (pinfunction "2_2") (pintype "passive"))
      (node (ref "S2") (pin "2") (pinfunction "2_2") (pintype "passive"))
    )
    (net (code "93") (name "SPI_CE_A") (class "Default")
      (node (ref "U10") (pin "21") (pinfunction "SPI_CS0_21") (pintype "output"))
      (node (ref "U21") (pin "1") (pinfunction "*CS_1") (pintype "passive"))
    )
    (net (code "94") (name "SPI_CE_B") (class "Default")
      (node (ref "U15") (pin "21") (pinfunction "SPI_CS0_21") (pintype "output"))
      (node (ref "U22") (pin "1") (pinfunction "*CS_1") (pintype "passive"))
    )
    (net (code "95") (name "SPI_SCK_A") (class "Default")
      (node (ref "U10") (pin "17") (pinfunction "SPI_SCLK_17") (pintype "output"))
      (node (ref "U21") (pin "6") (pinfunction "SCK_6") (pintype "bidirectional"))
    )
    (net (code "96") (name "SPI_SCK_B") (class "Default")
      (node (ref "U15") (pin "17") (pinfunction "SPI_SCLK_17") (pintype "output"))
      (node (ref "U22") (pin "6") (pinfunction "SCK_6") (pintype "bidirectional"))
    )
    (net (code "97") (name "SPI_SI_A") (class "Default")
      (node (ref "U10") (pin "20") (pinfunction "SPI_DATA_IN_20") (pintype "input"))
      (node (ref "U21") (pin "2") (pinfunction "SO_2") (pintype "output"))
    )
    (net (code "98") (name "SPI_SI_B") (class "Default")
      (node (ref "U15") (pin "20") (pinfunction "SPI_DATA_IN_20") (pintype "input"))
      (node (ref "U22") (pin "2") (pinfunction "SO_2") (pintype "output"))
    )
    (net (code "99") (name "SPI_SO_A") (class "Default")
      (node (ref "U10") (pin "18") (pinfunction "SPI_DATA_OUT_18") (pintype "output"))
      (node (ref "U21") (pin "5") (pinfunction "SI_5") (pintype "input"))
    )
    (net (code "100") (name "SPI_SO_B") (class "Default")
      (node (ref "U15") (pin "18") (pinfunction "SPI_DATA_OUT_18") (pintype "output"))
      (node (ref "U22") (pin "5") (pinfunction "SI_5") (pintype "input"))
    )
    (net (code "101") (name "S_RST") (class "Default")
      (node (ref "C173") (pin "2") (pinfunction "2_2") (pintype "passive"))
      (node (ref "R57") (pin "2") (pinfunction "2_2") (pintype "passive"))
      (node (ref "R71") (pin "2") (pinfunction "2_2") (pintype "passive"))
      (node (ref "U10") (pin "4") (pinfunction "GRSTZ_4") (pintype "input"))
      (node (ref "U15") (pin "4") (pinfunction "GRSTZ_4") (pintype "input"))
    )
    (net (code "102") (name "USB3-0-D_N") (class "Default")
      (node (ref "U7") (pin "27") (pinfunction "USB_DM_UP_27") (pintype "bidirectional"))
    )
    (net (code "103") (name "USB3-0-D_P") (class "Default")
      (node (ref "U7") (pin "26") (pinfunction "USB_DP_UP_26") (pintype "bidirectional"))
    )
    (net (code "104") (name "USB3-0-RX_N") (class "Default")
      (node (ref "C50") (pin "1") (pinfunction "1_1") (pintype "passive"))
    )
    (net (code "105") (name "USB3-0-RX_P") (class "Default")
      (node (ref "C48") (pin "1") (pinfunction "1_1") (pintype "passive"))
    )
    (net (code "106") (name "USB3-0-TX_N") (class "Default")
      (node (ref "U7") (pin "31") (pinfunction "USB_SSRXM_UP_31") (pintype "input"))
    )
    (net (code "107") (name "USB3-0-TX_P") (class "Default")
      (node (ref "U7") (pin "32") (pinfunction "USB_SSRXP_UP_32") (pintype "input"))
    )
    (net (code "108") (name "unconnected-(U7-FULLPWRMGMTZ{slash}SMBA1{slash}SS_UP-Pad36)") (class "Default")
      (node (ref "U7") (pin "36") (pinfunction "FULLPWRMGMTZ/SMBA1/SS_UP_36") (pintype "input"))
    )
    (net (code "109") (name "unconnected-(U7-OVERCUR1Z-Pad5)") (class "Default")
      (node (ref "U7") (pin "5") (pinfunction "OVERCUR1Z_5") (pintype "input"))
    )
    (net (code "110") (name "unconnected-(U7-OVERCUR2Z-Pad8)") (class "Default")
      (node (ref "U7") (pin "8") (pinfunction "OVERCUR2Z_8") (pintype "input"))
    )
    (net (code "111") (name "unconnected-(U7-PWRCTL1{slash}BATEN1-Pad4)") (class "Default")
      (node (ref "U7") (pin "4") (pinfunction "PWRCTL1/BATEN1_4") (pintype "bidirectional"))
    )
    (net (code "112") (name "unconnected-(U7-PWRCTL2{slash}BATEN2-Pad6)") (class "Default")
      (node (ref "U7") (pin "6") (pinfunction "PWRCTL2/BATEN2_6") (pintype "bidirectional"))
    )
    (net (code "113") (name "unconnected-(U7-SCL{slash}SMBCLK-Pad2)") (class "Default")
      (node (ref "U7") (pin "2") (pinfunction "SCL/SMBCLK_2") (pintype "bidirectional"))
    )
    (net (code "114") (name "unconnected-(U7-SDA{slash}SMBDAT-Pad3)") (class "Default")
      (node (ref "U7") (pin "3") (pinfunction "SDA/SMBDAT_3") (pintype "bidirectional"))
    )
    (net (code "115") (name "unconnected-(U7-SMBUSZ{slash}SS_DN2-Pad22)") (class "Default")
      (node (ref "U7") (pin "22") (pinfunction "SMBUSZ/SS_DN2_22") (pintype "input"))
    )
    (net (code "116") (name "unconnected-(U10-GPIO0-Pad8)") (class "Default")
      (node (ref "U10") (pin "8") (pinfunction "GPIO0_8") (pintype "bidirectional"))
    )
    (net (code "117") (name "unconnected-(U10-GPIO1-Pad9)") (class "Default")
      (node (ref "U10") (pin "9") (pinfunction "GPIO1_9") (pintype "bidirectional"))
    )
    (net (code "118") (name "unconnected-(U10-GPIO2-Pad10)") (class "Default")
      (node (ref "U10") (pin "10") (pinfunction "GPIO2_10") (pintype "bidirectional"))
    )
    (net (code "119") (name "unconnected-(U10-GPIO3-Pad11)") (class "Default")
      (node (ref "U10") (pin "11") (pinfunction "GPIO3_11") (pintype "bidirectional"))
    )
    (net (code "120") (name "unconnected-(U10-GPIO4-Pad13)") (class "Default")
      (node (ref "U10") (pin "13") (pinfunction "GPIO4_13") (pintype "bidirectional"))
    )
    (net (code "121") (name "unconnected-(U10-GPIO5-Pad14)") (class "Default")
      (node (ref "U10") (pin "14") (pinfunction "GPIO5_14") (pintype "bidirectional"))
    )
    (net (code "122") (name "unconnected-(U10-GPIO6-Pad15)") (class "Default")
      (node (ref "U10") (pin "15") (pinfunction "GPIO6_15") (pintype "bidirectional"))
    )
    (net (code "123") (name "unconnected-(U10-GPIO7-Pad16)") (class "Default")
      (node (ref "U10") (pin "16") (pinfunction "GPIO7_16") (pintype "bidirectional"))
    )
    (net (code "124") (name "unconnected-(U10-GPIO8{slash}UART_RX-Pad5)") (class "Default")
      (node (ref "U10") (pin "5") (pinfunction "GPIO8/UART_RX_5") (pintype "bidirectional"))
    )
    (net (code "125") (name "unconnected-(U10-GPIO9{slash}UART_TX-Pad6)") (class "Default")
      (node (ref "U10") (pin "6") (pinfunction "GPIO9/UART_TX_6") (pintype "bidirectional"))
    )
    (net (code "126") (name "unconnected-(U10-JTAG_TCK-Pad25)") (class "Default")
      (node (ref "U10") (pin "25") (pinfunction "JTAG_TCK_25") (pintype "input"))
    )
    (net (code "127") (name "unconnected-(U10-JTAG_TDI-Pad26)") (class "Default")
      (node (ref "U10") (pin "26") (pinfunction "JTAG_TDI_26") (pintype "input"))
    )
    (net (code "128") (name "unconnected-(U10-JTAG_TDO-Pad27)") (class "Default")
      (node (ref "U10") (pin "27") (pinfunction "JTAG_TDO_27") (pintype "output"))
    )
    (net (code "129") (name "unconnected-(U10-JTAG_TMS-Pad28)") (class "Default")
      (node (ref "U10") (pin "28") (pinfunction "JTAG_TMS_28") (pintype "input"))
    )
    (net (code "130") (name "unconnected-(U10-JTAG_TRSTZ-Pad29)") (class "Default")
      (node (ref "U10") (pin "29") (pinfunction "JTAG_TRSTZ_29") (pintype "input"))
    )
    (net (code "131") (name "unconnected-(U10-SPI_CS1{slash}GPIO10-Pad22)") (class "Default")
      (node (ref "U10") (pin "22") (pinfunction "SPI_CS1/GPIO10_22") (pintype "bidirectional"))
    )
    (net (code "132") (name "unconnected-(U10-SPI_CS2{slash}GPIO11-Pad23)") (class "Default")
      (node (ref "U10") (pin "23") (pinfunction "SPI_CS2/GPIO11_23") (pintype "bidirectional"))
    )
    (net (code "133") (name "unconnected-(U10-VSSOSC-Pad53)") (class "Default")
      (node (ref "U10") (pin "53") (pinfunction "VSSOSC_53") (pintype "power_in"))
    )
    (net (code "134") (name "unconnected-(U15-GPIO0-Pad8)") (class "Default")
      (node (ref "U15") (pin "8") (pinfunction "GPIO0_8") (pintype "bidirectional"))
    )
    (net (code "135") (name "unconnected-(U15-GPIO1-Pad9)") (class "Default")
      (node (ref "U15") (pin "9") (pinfunction "GPIO1_9") (pintype "bidirectional"))
    )
    (net (code "136") (name "unconnected-(U15-GPIO2-Pad10)") (class "Default")
      (node (ref "U15") (pin "10") (pinfunction "GPIO2_10") (pintype "bidirectional"))
    )
    (net (code "137") (name "unconnected-(U15-GPIO3-Pad11)") (class "Default")
      (node (ref "U15") (pin "11") (pinfunction "GPIO3_11") (pintype "bidirectional"))
    )
    (net (code "138") (name "unconnected-(U15-GPIO4-Pad13)") (class "Default")
      (node (ref "U15") (pin "13") (pinfunction "GPIO4_13") (pintype "bidirectional"))
    )
    (net (code "139") (name "unconnected-(U15-GPIO5-Pad14)") (class "Default")
      (node (ref "U15") (pin "14") (pinfunction "GPIO5_14") (pintype "bidirectional"))
    )
    (net (code "140") (name "unconnected-(U15-GPIO6-Pad15)") (class "Default")
      (node (ref "U15") (pin "15") (pinfunction "GPIO6_15") (pintype "bidirectional"))
    )
    (net (code "141") (name "unconnected-(U15-GPIO7-Pad16)") (class "Default")
      (node (ref "U15") (pin "16") (pinfunction "GPIO7_16") (pintype "bidirectional"))
    )
    (net (code "142") (name "unconnected-(U15-GPIO8{slash}UART_RX-Pad5)") (class "Default")
      (node (ref "U15") (pin "5") (pinfunction "GPIO8/UART_RX_5") (pintype "bidirectional"))
    )
    (net (code "143") (name "unconnected-(U15-GPIO9{slash}UART_TX-Pad6)") (class "Default")
      (node (ref "U15") (pin "6") (pinfunction "GPIO9/UART_TX_6") (pintype "bidirectional"))
    )
    (net (code "144") (name "unconnected-(U15-JTAG_TCK-Pad25)") (class "Default")
      (node (ref "U15") (pin "25") (pinfunction "JTAG_TCK_25") (pintype "input"))
    )
    (net (code "145") (name "unconnected-(U15-JTAG_TDI-Pad26)") (class "Default")
      (node (ref "U15") (pin "26") (pinfunction "JTAG_TDI_26") (pintype "input"))
    )
    (net (code "146") (name "unconnected-(U15-JTAG_TDO-Pad27)") (class "Default")
      (node (ref "U15") (pin "27") (pinfunction "JTAG_TDO_27") (pintype "output"))
    )
    (net (code "147") (name "unconnected-(U15-JTAG_TMS-Pad28)") (class "Default")
      (node (ref "U15") (pin "28") (pinfunction "JTAG_TMS_28") (pintype "input"))
    )
    (net (code "148") (name "unconnected-(U15-JTAG_TRSTZ-Pad29)") (class "Default")
      (node (ref "U15") (pin "29") (pinfunction "JTAG_TRSTZ_29") (pintype "input"))
    )
    (net (code "149") (name "unconnected-(U15-SPI_CS1{slash}GPIO10-Pad22)") (class "Default")
      (node (ref "U15") (pin "22") (pinfunction "SPI_CS1/GPIO10_22") (pintype "bidirectional"))
    )
    (net (code "150") (name "unconnected-(U15-SPI_CS2{slash}GPIO11-Pad23)") (class "Default")
      (node (ref "U15") (pin "23") (pinfunction "SPI_CS2/GPIO11_23") (pintype "bidirectional"))
    )
    (net (code "151") (name "unconnected-(U15-VSSOSC-Pad53)") (class "Default")
      (node (ref "U15") (pin "53") (pinfunction "VSSOSC_53") (pintype "power_in"))
    )
    (net (code "152") (name "unconnected-(U25-MR_N-Pad4)") (class "Default")
      (node (ref "U25") (pin "4") (pinfunction "MR_N_4") (pintype "input"))
    )
  )
)
